# lora_gateway_sx1302_pcie_module_v1_1_868.net
KiCad netlist of a schematic drawn in EAGLE
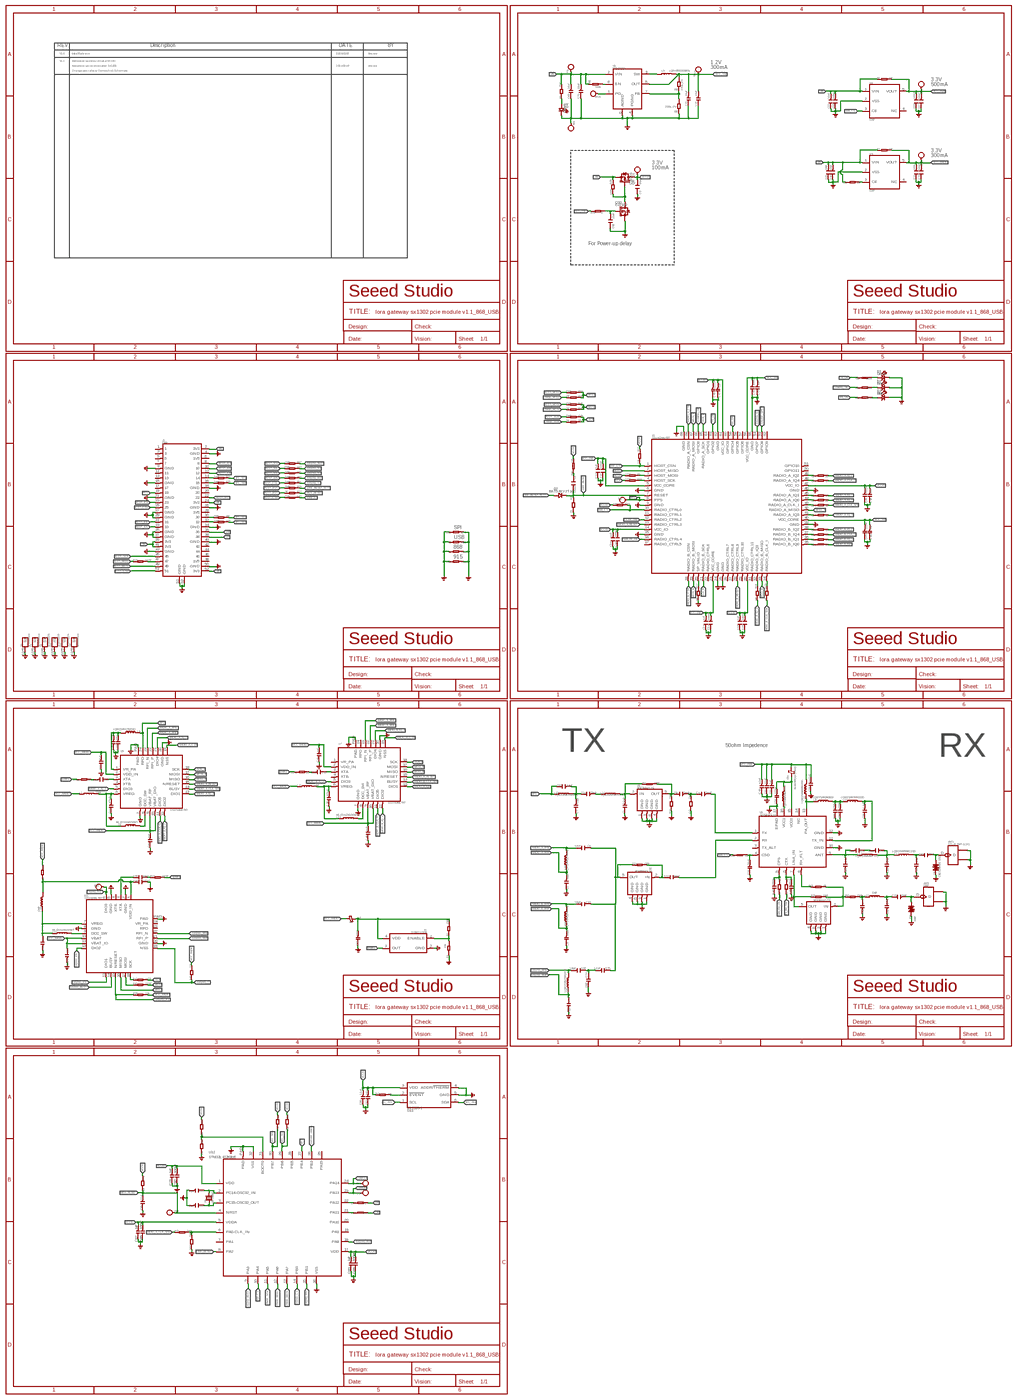
[diagram p0: schematic, sheet 1, overview]
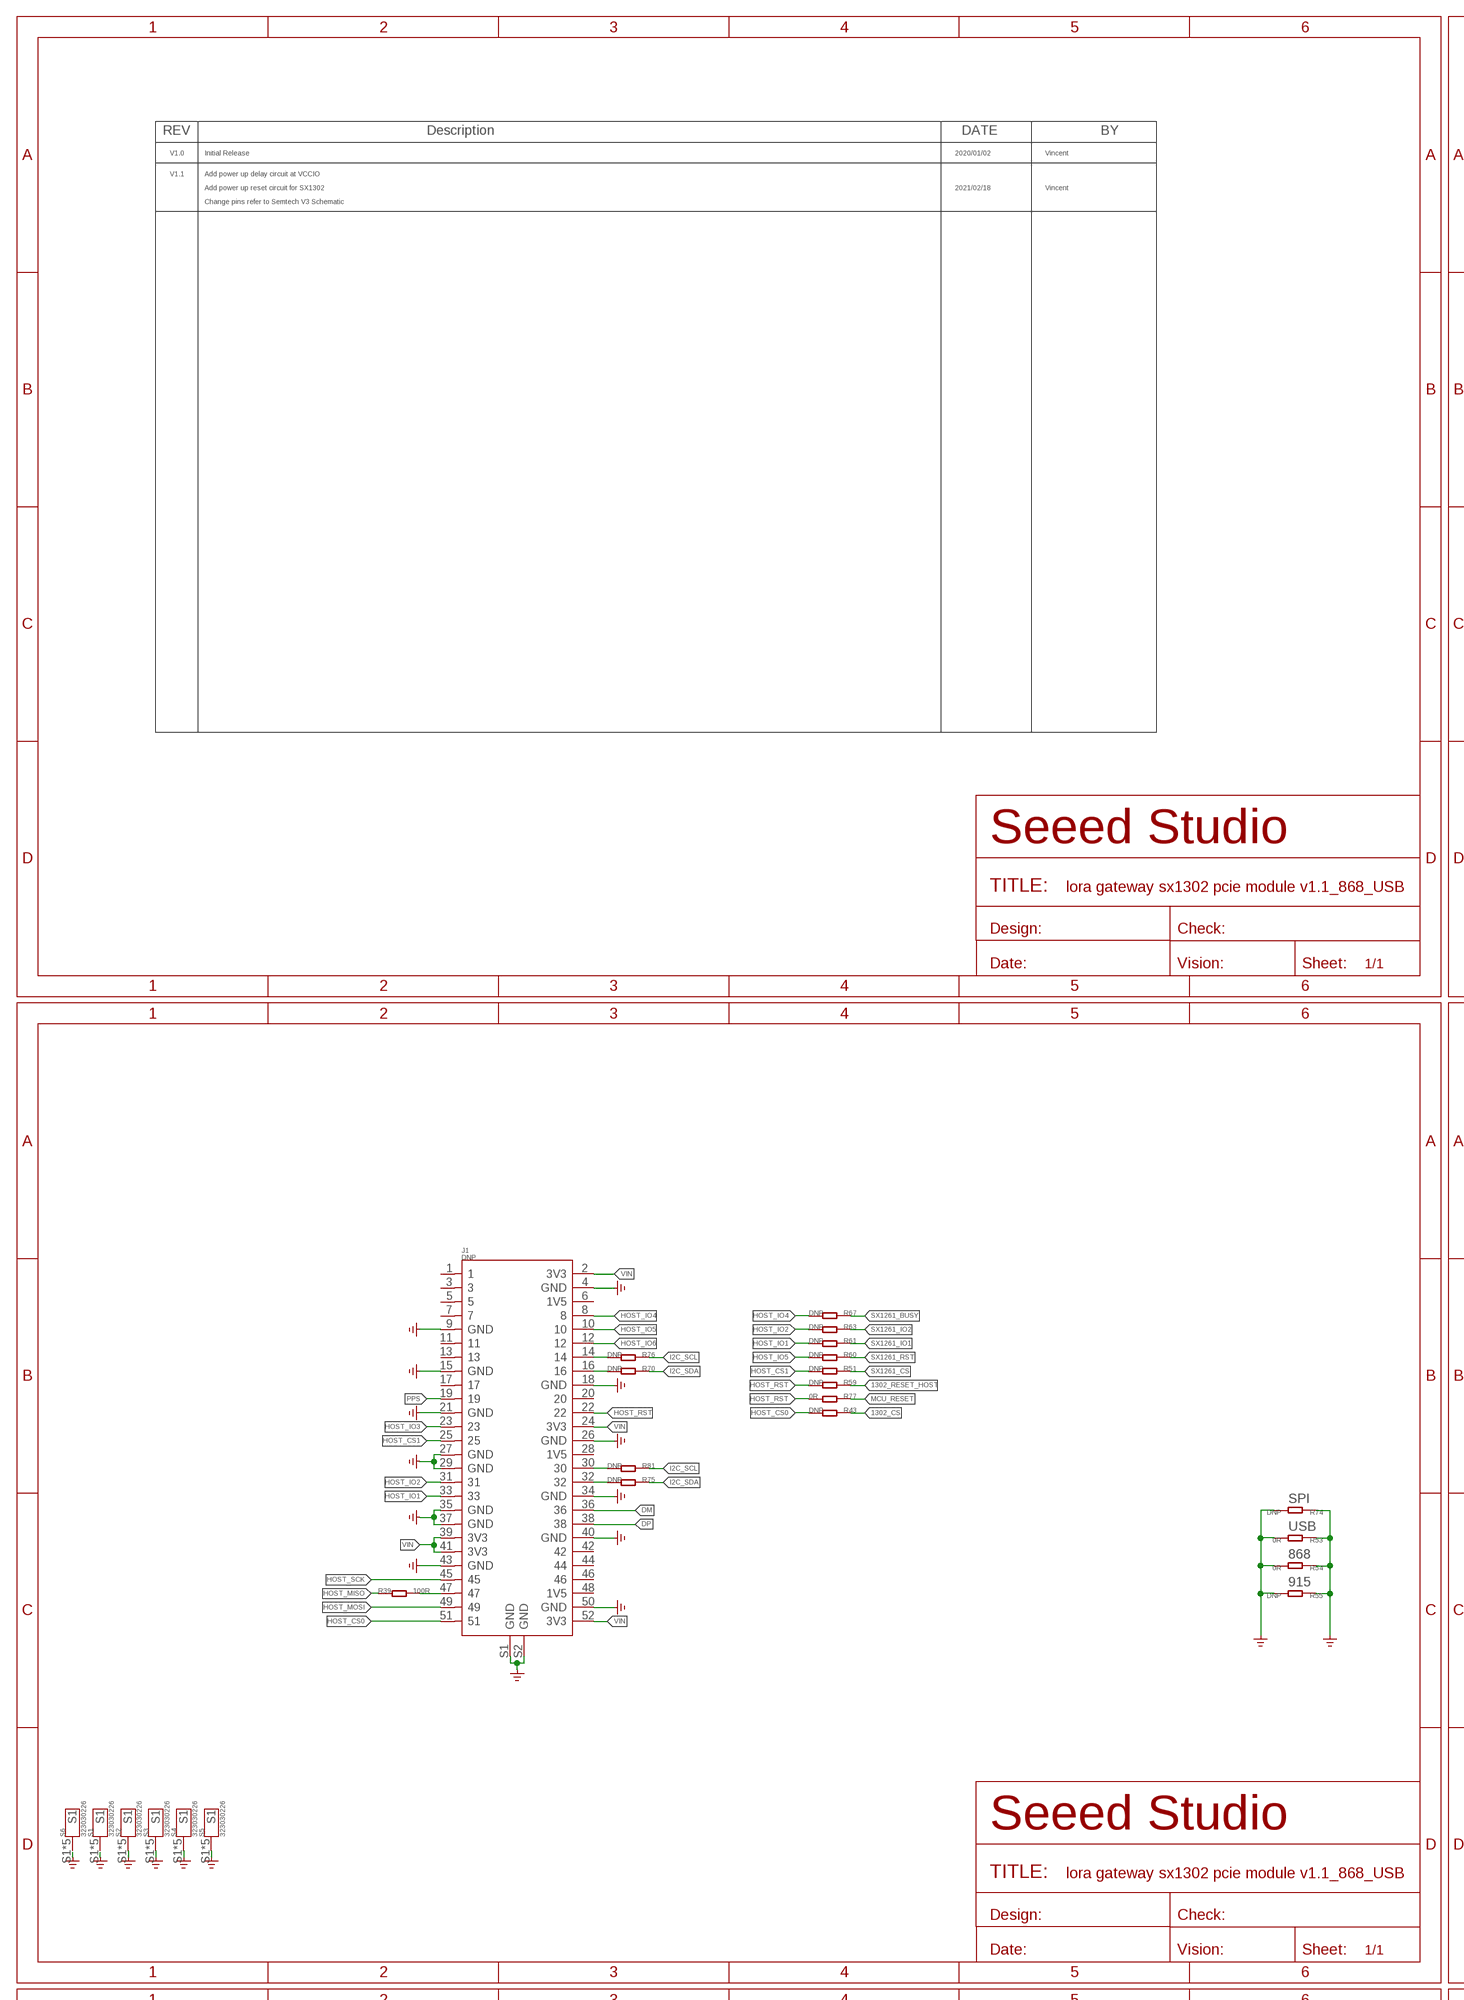
[diagram p1: schematic, sheet 1, part 1 of 4]
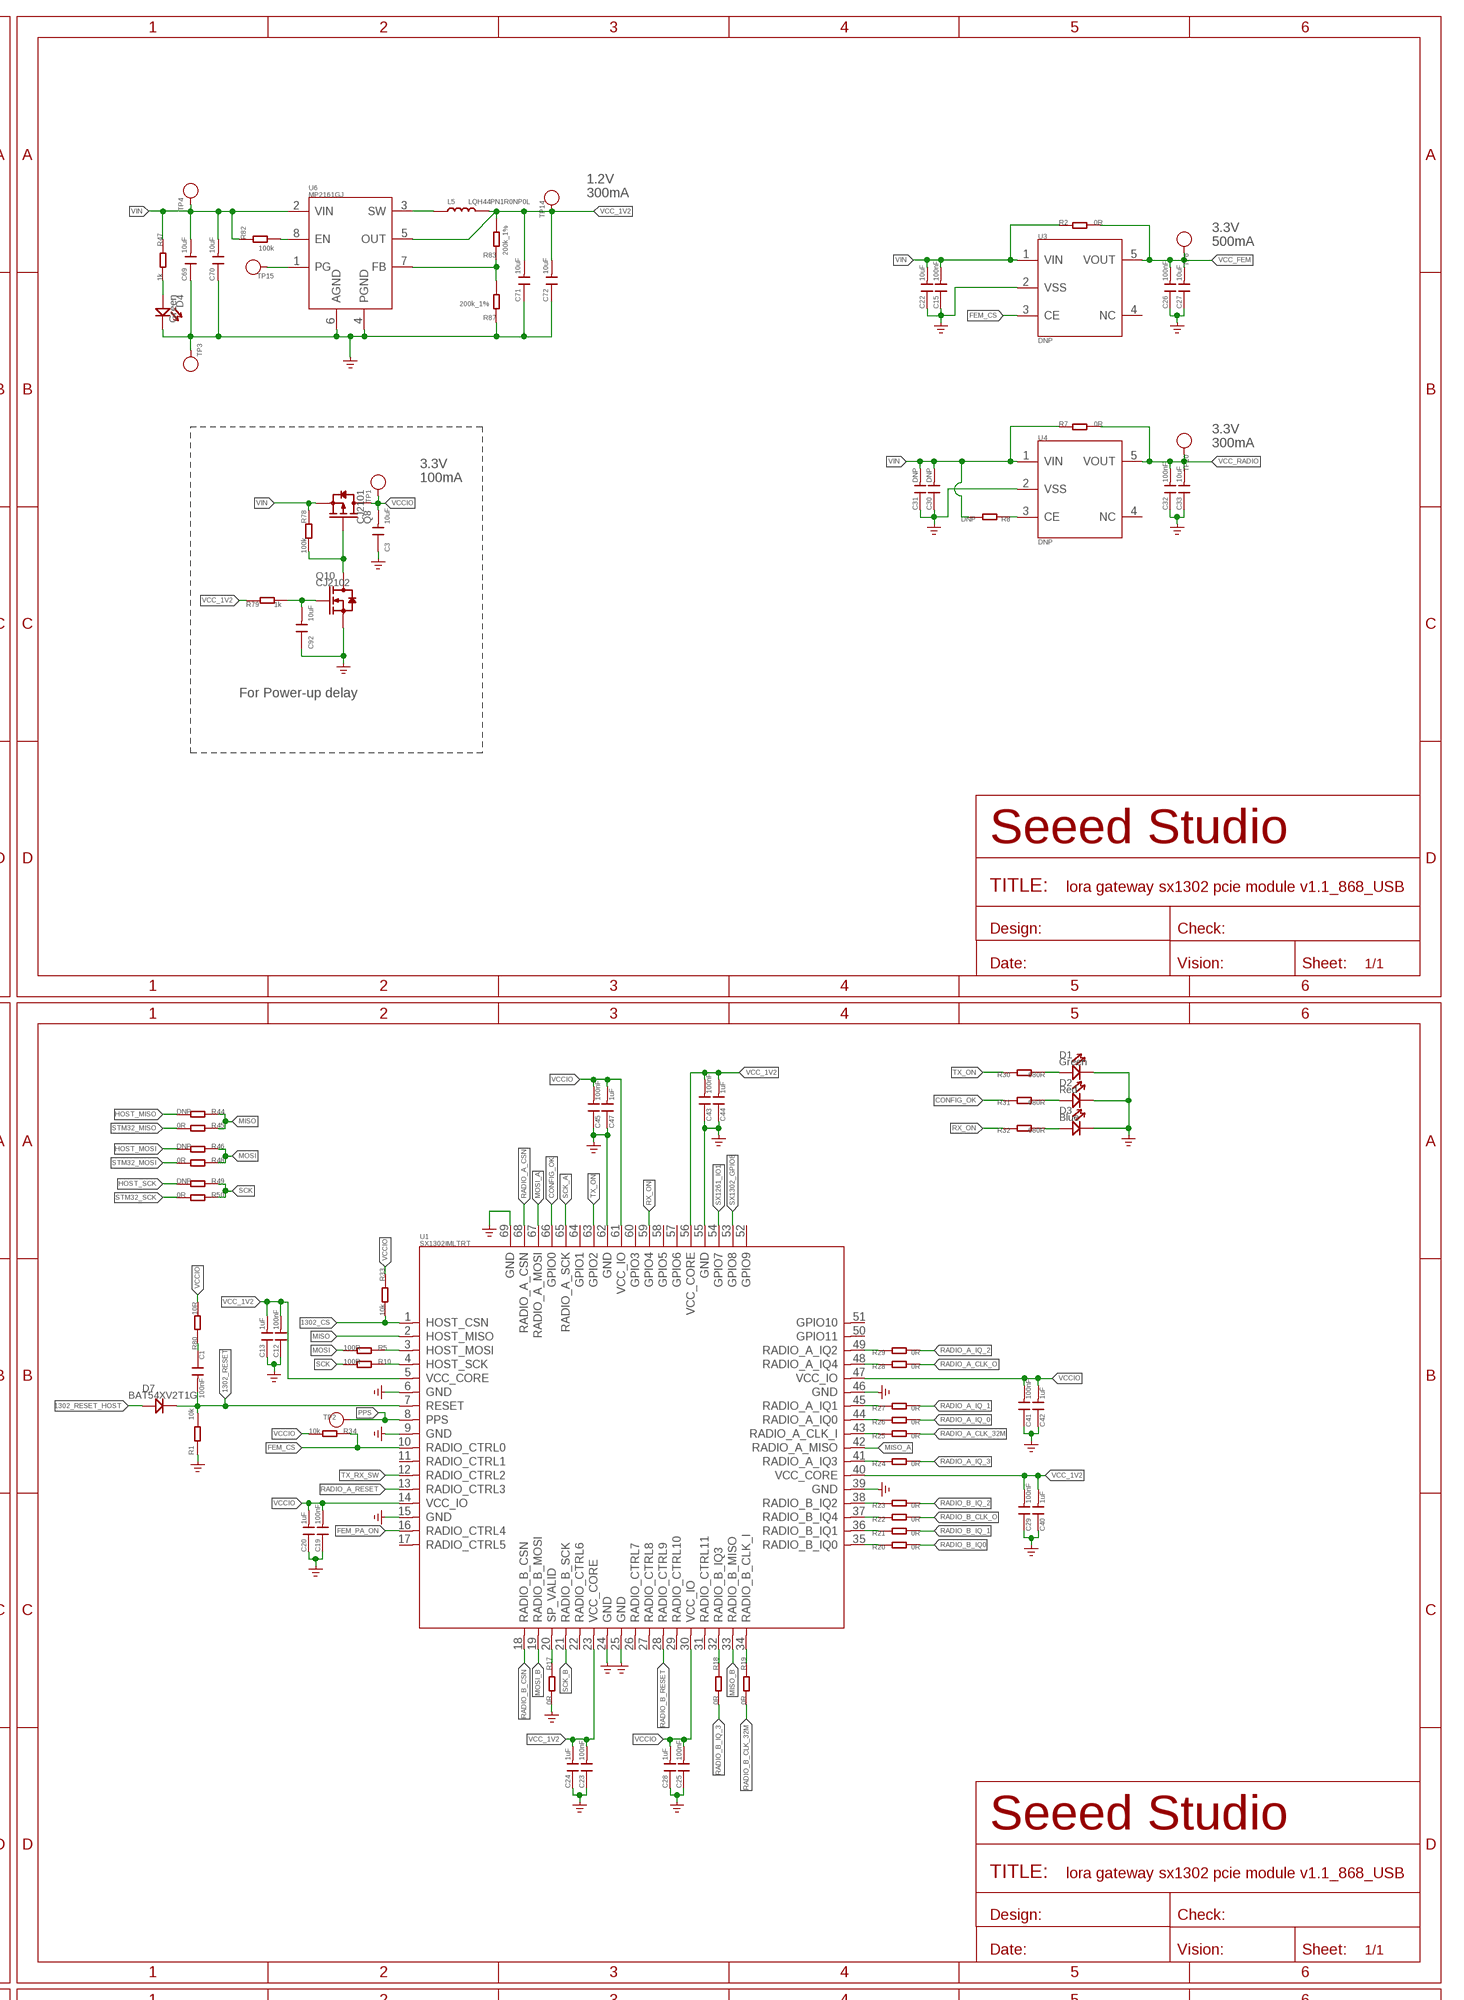
[diagram p2: schematic, sheet 1, part 2 of 4]
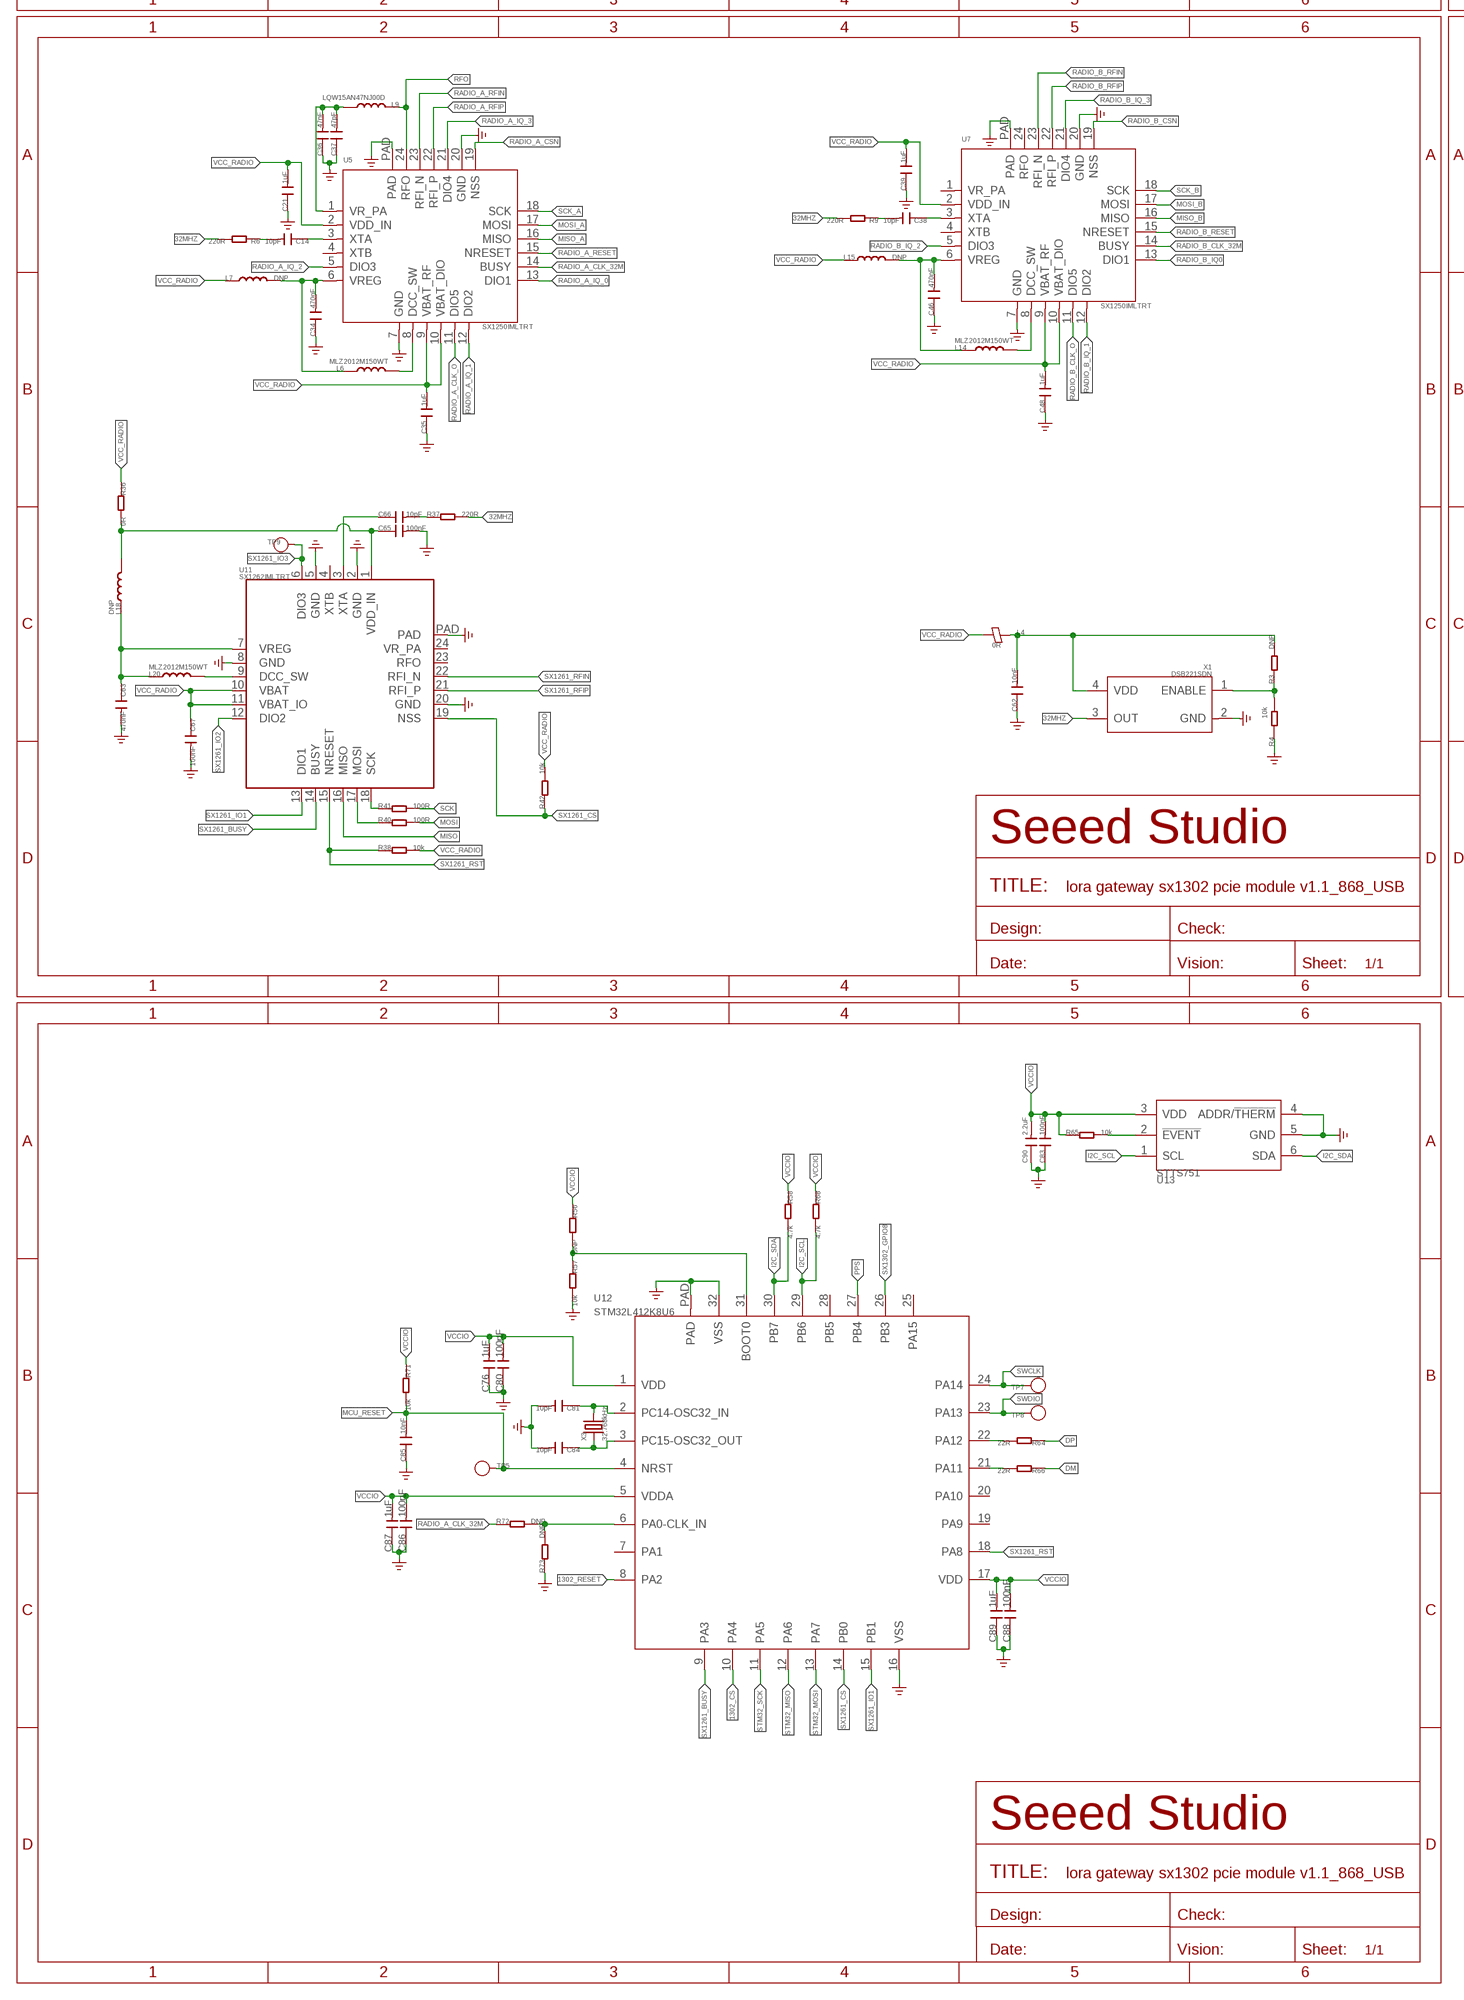
[diagram p3: schematic, sheet 1, part 3 of 4]
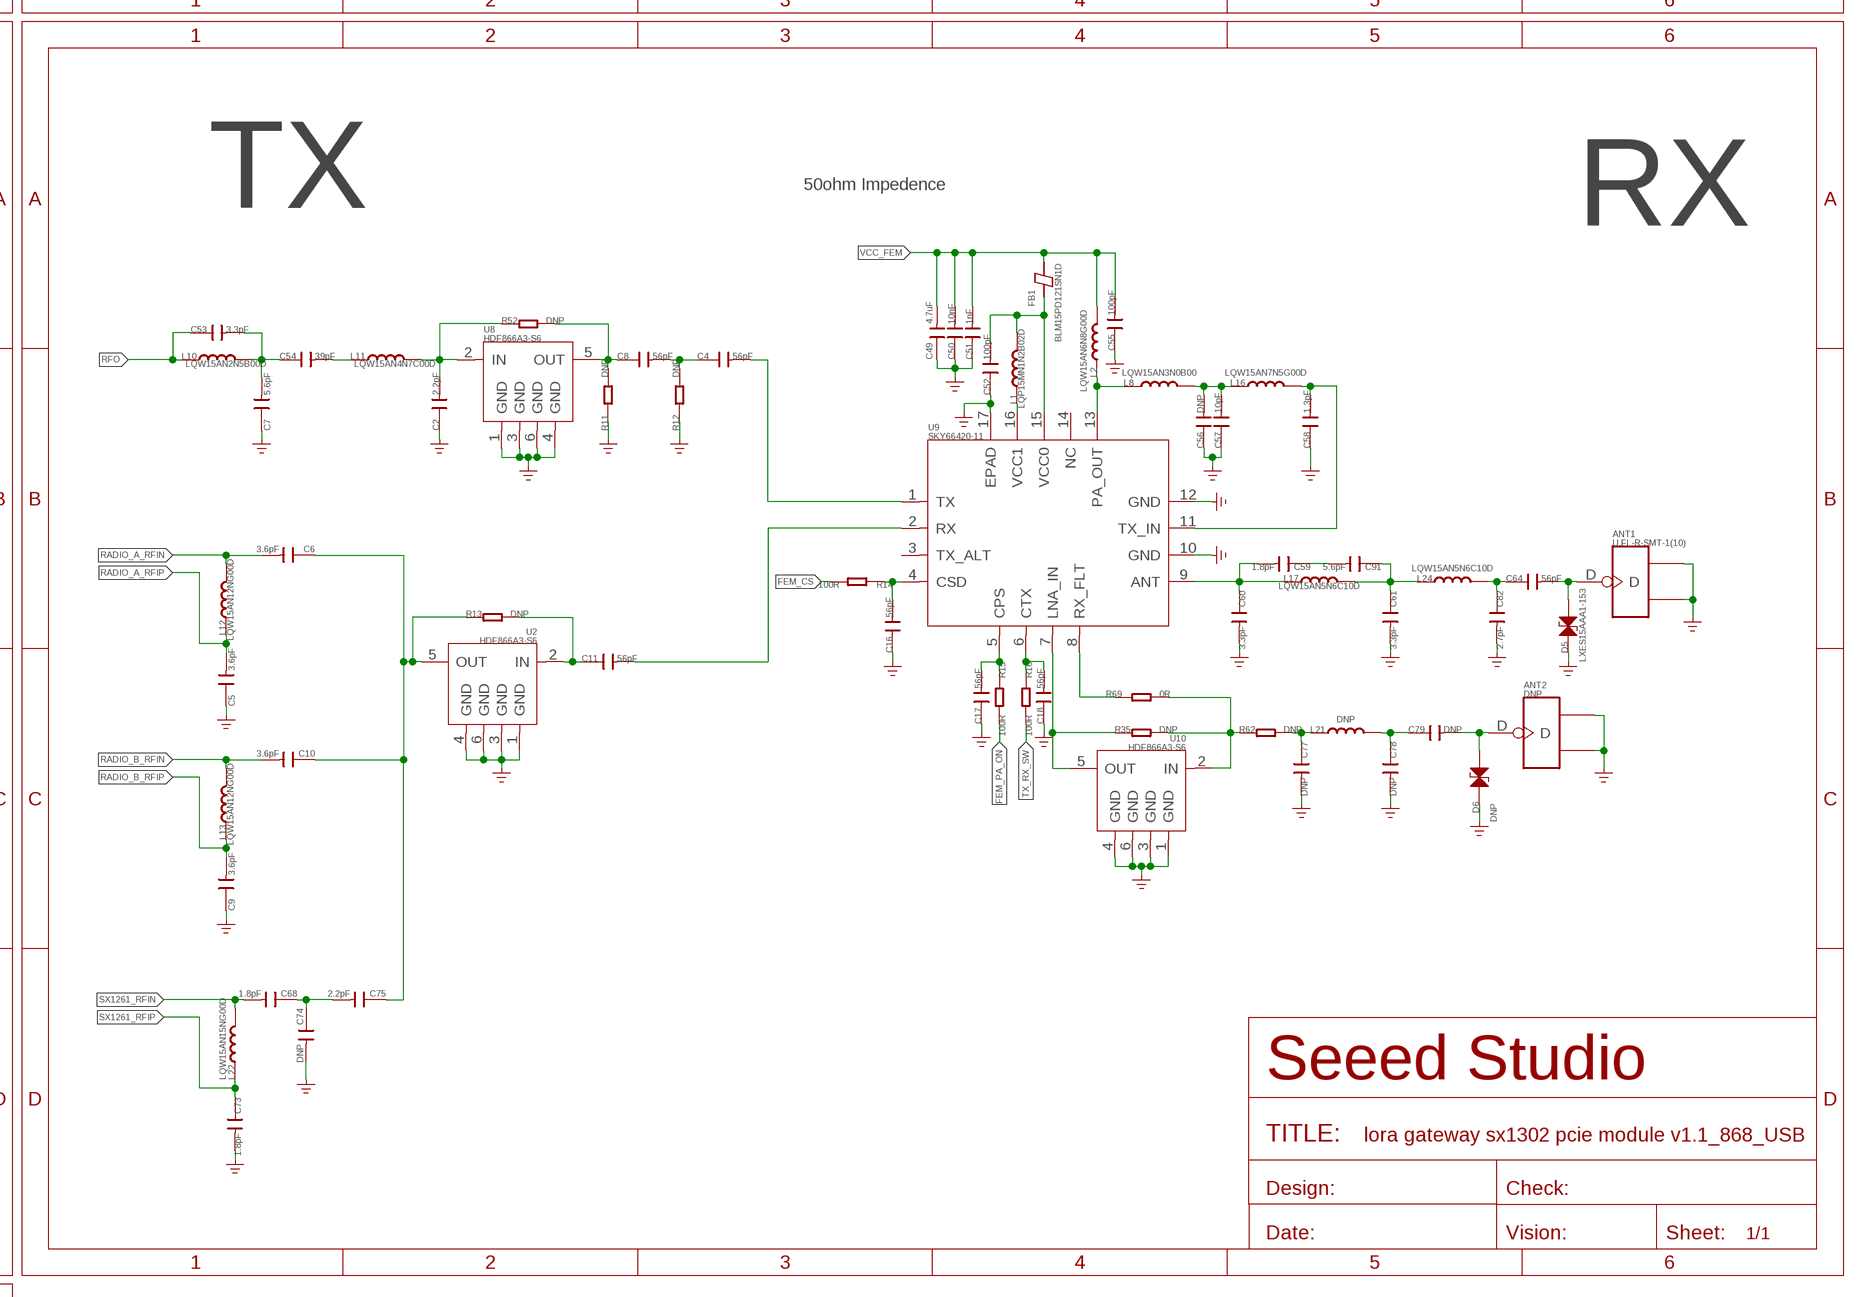
[diagram p4: schematic, sheet 1, part 4 of 4]

(export (version "E")
  (design (tool "Eeschema 10.0.6"))
  (components
    (comp (ref "ANT1")
      (value "U.FL-R-SMT-1(10)")
      (footprint "eagle-import:U-FL3P-SMD-2.6X2.6X1.0MM")
      (fields (field (name "SPICEPREFIX") "J"))
      (libsource (lib "eagle-import") (part "ANTENNA-U-FL-320110048"))
    )
    (comp (ref "ANT2")
      (value "DNP")
      (footprint "eagle-import:U-FL3P-SMD-2.6X2.6X1.0MM")
      (fields (field (name "SPICEPREFIX") "J"))
      (libsource (lib "eagle-import") (part "ANTENNA-U-FL-320110048"))
    )
    (comp (ref "C1")
      (value "100nF")
      (footprint "eagle-import:C0402")
      (libsource (lib "eagle-import") (part "C-0402"))
    )
    (comp (ref "C2")
      (value "2.2pF")
      (footprint "eagle-import:C0402")
      (libsource (lib "eagle-import") (part "C-0402"))
    )
    (comp (ref "C3")
      (value "10uF")
      (footprint "eagle-import:C0603")
      (libsource (lib "eagle-import") (part "C-0603"))
    )
    (comp (ref "C4")
      (value "56pF")
      (footprint "eagle-import:C0402")
      (libsource (lib "eagle-import") (part "C-0402"))
    )
    (comp (ref "C5")
      (value "3.6pF")
      (footprint "eagle-import:C0402")
      (libsource (lib "eagle-import") (part "C-0402"))
    )
    (comp (ref "C6")
      (value "3.6pF")
      (footprint "eagle-import:C0402")
      (libsource (lib "eagle-import") (part "C-0402"))
    )
    (comp (ref "C7")
      (value "5.6pF")
      (footprint "eagle-import:C0402")
      (libsource (lib "eagle-import") (part "C-0402"))
    )
    (comp (ref "C8")
      (value "56pF")
      (footprint "eagle-import:C0402")
      (libsource (lib "eagle-import") (part "C-0402"))
    )
    (comp (ref "C9")
      (value "3.6pF")
      (footprint "eagle-import:C0402")
      (libsource (lib "eagle-import") (part "C-0402"))
    )
    (comp (ref "C10")
      (value "3.6pF")
      (footprint "eagle-import:C0402")
      (libsource (lib "eagle-import") (part "C-0402"))
    )
    (comp (ref "C11")
      (value "56pF")
      (footprint "eagle-import:C0402")
      (libsource (lib "eagle-import") (part "C-0402"))
    )
    (comp (ref "C12")
      (value "100nF")
      (footprint "eagle-import:C0402")
      (libsource (lib "eagle-import") (part "C-0402"))
    )
    (comp (ref "C13")
      (value "1uF")
      (footprint "eagle-import:C0402")
      (libsource (lib "eagle-import") (part "C-0402"))
    )
    (comp (ref "C14")
      (value "10pF")
      (footprint "eagle-import:C0402")
      (libsource (lib "eagle-import") (part "C-0402"))
    )
    (comp (ref "C15")
      (value "100nF")
      (footprint "eagle-import:C0402")
      (libsource (lib "eagle-import") (part "C-0402"))
    )
    (comp (ref "C16")
      (value "56pF")
      (footprint "eagle-import:C0402")
      (libsource (lib "eagle-import") (part "C-0402"))
    )
    (comp (ref "C17")
      (value "56pF")
      (footprint "eagle-import:C0402")
      (libsource (lib "eagle-import") (part "C-0402"))
    )
    (comp (ref "C18")
      (value "56pF")
      (footprint "eagle-import:C0402")
      (libsource (lib "eagle-import") (part "C-0402"))
    )
    (comp (ref "C19")
      (value "100nF")
      (footprint "eagle-import:C0402")
      (libsource (lib "eagle-import") (part "C-0402"))
    )
    (comp (ref "C20")
      (value "1uF")
      (footprint "eagle-import:C0402")
      (libsource (lib "eagle-import") (part "C-0402"))
    )
    (comp (ref "C21")
      (value "1uF")
      (footprint "eagle-import:C0402")
      (libsource (lib "eagle-import") (part "C-0402"))
    )
    (comp (ref "C22")
      (value "10uF")
      (footprint "eagle-import:C0603@1")
      (libsource (lib "eagle-import") (part "CAP-0603"))
    )
    (comp (ref "C23")
      (value "100nF")
      (footprint "eagle-import:C0402")
      (libsource (lib "eagle-import") (part "C-0402"))
    )
    (comp (ref "C24")
      (value "1uF")
      (footprint "eagle-import:C0402")
      (libsource (lib "eagle-import") (part "C-0402"))
    )
    (comp (ref "C25")
      (value "100nF")
      (footprint "eagle-import:C0402")
      (libsource (lib "eagle-import") (part "C-0402"))
    )
    (comp (ref "C26")
      (value "100nF")
      (footprint "eagle-import:C0402")
      (libsource (lib "eagle-import") (part "C-0402"))
    )
    (comp (ref "C27")
      (value "10uF")
      (footprint "eagle-import:C0603@1")
      (libsource (lib "eagle-import") (part "CAP-0603"))
    )
    (comp (ref "C28")
      (value "1uF")
      (footprint "eagle-import:C0402")
      (libsource (lib "eagle-import") (part "C-0402"))
    )
    (comp (ref "C29")
      (value "100nF")
      (footprint "eagle-import:C0402")
      (libsource (lib "eagle-import") (part "C-0402"))
    )
    (comp (ref "C30")
      (value "DNP")
      (footprint "eagle-import:C0402")
      (libsource (lib "eagle-import") (part "C-0402"))
    )
    (comp (ref "C31")
      (value "DNP")
      (footprint "eagle-import:C0603@1")
      (libsource (lib "eagle-import") (part "CAP-0603"))
    )
    (comp (ref "C32")
      (value "100nF")
      (footprint "eagle-import:C0402")
      (libsource (lib "eagle-import") (part "C-0402"))
    )
    (comp (ref "C33")
      (value "10uF")
      (footprint "eagle-import:C0603@1")
      (libsource (lib "eagle-import") (part "CAP-0603"))
    )
    (comp (ref "C34")
      (value "470nF")
      (footprint "eagle-import:C0402")
      (libsource (lib "eagle-import") (part "C-0402"))
    )
    (comp (ref "C35")
      (value "1uF")
      (footprint "eagle-import:C0402")
      (libsource (lib "eagle-import") (part "C-0402"))
    )
    (comp (ref "C36")
      (value "47nF")
      (footprint "eagle-import:C0402")
      (libsource (lib "eagle-import") (part "C-0402"))
    )
    (comp (ref "C37")
      (value "47pF")
      (footprint "eagle-import:C0402")
      (libsource (lib "eagle-import") (part "C-0402"))
    )
    (comp (ref "C38")
      (value "10pF")
      (footprint "eagle-import:C0402")
      (libsource (lib "eagle-import") (part "C-0402"))
    )
    (comp (ref "C39")
      (value "1uF")
      (footprint "eagle-import:C0402")
      (libsource (lib "eagle-import") (part "C-0402"))
    )
    (comp (ref "C40")
      (value "1uF")
      (footprint "eagle-import:C0402")
      (libsource (lib "eagle-import") (part "C-0402"))
    )
    (comp (ref "C41")
      (value "100nF")
      (footprint "eagle-import:C0402")
      (libsource (lib "eagle-import") (part "C-0402"))
    )
    (comp (ref "C42")
      (value "1uF")
      (footprint "eagle-import:C0402")
      (libsource (lib "eagle-import") (part "C-0402"))
    )
    (comp (ref "C43")
      (value "100nF")
      (footprint "eagle-import:C0402")
      (libsource (lib "eagle-import") (part "C-0402"))
    )
    (comp (ref "C44")
      (value "1uF")
      (footprint "eagle-import:C0402")
      (libsource (lib "eagle-import") (part "C-0402"))
    )
    (comp (ref "C45")
      (value "100nF")
      (footprint "eagle-import:C0402")
      (libsource (lib "eagle-import") (part "C-0402"))
    )
    (comp (ref "C46")
      (value "470nF")
      (footprint "eagle-import:C0402")
      (libsource (lib "eagle-import") (part "C-0402"))
    )
    (comp (ref "C47")
      (value "1uF")
      (footprint "eagle-import:C0402")
      (libsource (lib "eagle-import") (part "C-0402"))
    )
    (comp (ref "C48")
      (value "1uF")
      (footprint "eagle-import:C0402")
      (libsource (lib "eagle-import") (part "C-0402"))
    )
    (comp (ref "C49")
      (value "4.7uF")
      (footprint "eagle-import:C0603")
      (libsource (lib "eagle-import") (part "C-0603"))
    )
    (comp (ref "C50")
      (value "10nF")
      (footprint "eagle-import:C0402")
      (libsource (lib "eagle-import") (part "C-0402"))
    )
    (comp (ref "C51")
      (value "1nF")
      (footprint "eagle-import:C0402")
      (libsource (lib "eagle-import") (part "C-0402"))
    )
    (comp (ref "C52")
      (value "100pF")
      (footprint "eagle-import:C0402")
      (libsource (lib "eagle-import") (part "C-0402"))
    )
    (comp (ref "C53")
      (value "3.3pF")
      (footprint "eagle-import:C0402")
      (libsource (lib "eagle-import") (part "C-0402"))
    )
    (comp (ref "C54")
      (value "39pF")
      (footprint "eagle-import:C0402")
      (libsource (lib "eagle-import") (part "C-0402"))
    )
    (comp (ref "C55")
      (value "100pF")
      (footprint "eagle-import:C0402")
      (fields (field (name "SPICEPREFIX") "C"))
      (libsource (lib "eagle-import") (part "C-0402"))
    )
    (comp (ref "C56")
      (value "DNP")
      (footprint "eagle-import:C0402")
      (libsource (lib "eagle-import") (part "C-0402"))
    )
    (comp (ref "C57")
      (value "10pF")
      (footprint "eagle-import:C0402")
      (libsource (lib "eagle-import") (part "C-0402"))
    )
    (comp (ref "C58")
      (value "1.3pF")
      (footprint "eagle-import:C0402")
      (libsource (lib "eagle-import") (part "C-0402"))
    )
    (comp (ref "C59")
      (value "1.8pF")
      (footprint "eagle-import:C0402")
      (libsource (lib "eagle-import") (part "C-0402"))
    )
    (comp (ref "C60")
      (value "3.3pF")
      (footprint "eagle-import:C0402")
      (libsource (lib "eagle-import") (part "C-0402"))
    )
    (comp (ref "C61")
      (value "3.3pF")
      (footprint "eagle-import:C0402")
      (libsource (lib "eagle-import") (part "C-0402"))
    )
    (comp (ref "C62")
      (value "10nF")
      (footprint "eagle-import:C0402")
      (libsource (lib "eagle-import") (part "C-0402"))
    )
    (comp (ref "C63")
      (value "470nF")
      (footprint "eagle-import:C0402")
      (libsource (lib "eagle-import") (part "C-0402"))
    )
    (comp (ref "C64")
      (value "56pF")
      (footprint "eagle-import:C0402")
      (libsource (lib "eagle-import") (part "C-0402"))
    )
    (comp (ref "C65")
      (value "100nF")
      (footprint "eagle-import:C0402")
      (libsource (lib "eagle-import") (part "C-0402"))
    )
    (comp (ref "C66")
      (value "10pF")
      (footprint "eagle-import:C0402")
      (libsource (lib "eagle-import") (part "C-0402"))
    )
    (comp (ref "C67")
      (value "100nF")
      (footprint "eagle-import:C0402")
      (libsource (lib "eagle-import") (part "C-0402"))
    )
    (comp (ref "C68")
      (value "1.8pF")
      (footprint "eagle-import:C0402")
      (libsource (lib "eagle-import") (part "C-0402"))
    )
    (comp (ref "C69")
      (value "10uF")
      (footprint "eagle-import:C0805")
      (libsource (lib "eagle-import") (part "CAP-0805"))
    )
    (comp (ref "C70")
      (value "10uF")
      (footprint "eagle-import:C0805")
      (libsource (lib "eagle-import") (part "CAP-0805"))
    )
    (comp (ref "C71")
      (value "10uF")
      (footprint "eagle-import:C0805")
      (libsource (lib "eagle-import") (part "CAP-0805"))
    )
    (comp (ref "C72")
      (value "10uF")
      (footprint "eagle-import:C0805")
      (libsource (lib "eagle-import") (part "CAP-0805"))
    )
    (comp (ref "C73")
      (value "1.8pF")
      (footprint "eagle-import:C0402")
      (libsource (lib "eagle-import") (part "C-0402"))
    )
    (comp (ref "C74")
      (value "DNP")
      (footprint "eagle-import:C0402")
      (libsource (lib "eagle-import") (part "C-0402"))
    )
    (comp (ref "C75")
      (value "2.2pF")
      (footprint "eagle-import:C0402")
      (libsource (lib "eagle-import") (part "C-0402"))
    )
    (comp (ref "C76")
      (value "1uF")
      (footprint "eagle-import:C0402")
      (libsource (lib "eagle-import") (part "C-0402"))
    )
    (comp (ref "C77")
      (value "DNP")
      (footprint "eagle-import:C0402")
      (libsource (lib "eagle-import") (part "C-0402"))
    )
    (comp (ref "C78")
      (value "DNP")
      (footprint "eagle-import:C0402")
      (libsource (lib "eagle-import") (part "C-0402"))
    )
    (comp (ref "C79")
      (value "DNP")
      (footprint "eagle-import:C0402")
      (libsource (lib "eagle-import") (part "C-0402"))
    )
    (comp (ref "C80")
      (value "100nF")
      (footprint "eagle-import:C0402")
      (libsource (lib "eagle-import") (part "C-0402"))
    )
    (comp (ref "C81")
      (value "10pF")
      (footprint "eagle-import:C0402")
      (libsource (lib "eagle-import") (part "C-0402"))
    )
    (comp (ref "C82")
      (value "2.7pF")
      (footprint "eagle-import:C0402")
      (libsource (lib "eagle-import") (part "C-0402"))
    )
    (comp (ref "C83")
      (value "100nF")
      (footprint "eagle-import:C0402")
      (libsource (lib "eagle-import") (part "C-0402"))
    )
    (comp (ref "C84")
      (value "10pF")
      (footprint "eagle-import:C0402")
      (libsource (lib "eagle-import") (part "C-0402"))
    )
    (comp (ref "C85")
      (value "10nF")
      (footprint "eagle-import:C0402")
      (libsource (lib "eagle-import") (part "C-0402"))
    )
    (comp (ref "C86")
      (value "100nF")
      (footprint "eagle-import:C0402")
      (libsource (lib "eagle-import") (part "C-0402"))
    )
    (comp (ref "C87")
      (value "1uF")
      (footprint "eagle-import:C0402")
      (libsource (lib "eagle-import") (part "C-0402"))
    )
    (comp (ref "C88")
      (value "100nF")
      (footprint "eagle-import:C0402")
      (libsource (lib "eagle-import") (part "C-0402"))
    )
    (comp (ref "C89")
      (value "1uF")
      (footprint "eagle-import:C0402")
      (libsource (lib "eagle-import") (part "C-0402"))
    )
    (comp (ref "C90")
      (value "2.2uF")
      (footprint "eagle-import:C0603")
      (libsource (lib "eagle-import") (part "C-0603"))
    )
    (comp (ref "C91")
      (value "5.6pF")
      (footprint "eagle-import:C0402")
      (libsource (lib "eagle-import") (part "C-0402"))
    )
    (comp (ref "C92")
      (value "10uF")
      (footprint "eagle-import:C0603")
      (libsource (lib "eagle-import") (part "C-0603"))
    )
    (comp (ref "D1")
      (value "Green")
      (footprint "eagle-import:LED-0402")
      (libsource (lib "eagle-import") (part "LED-0402"))
    )
    (comp (ref "D2")
      (value "Red")
      (footprint "eagle-import:LED-0402")
      (libsource (lib "eagle-import") (part "LED-0402"))
    )
    (comp (ref "D3")
      (value "Blue")
      (footprint "eagle-import:LED-0402")
      (libsource (lib "eagle-import") (part "LED-0402"))
    )
    (comp (ref "D4")
      (value "Green")
      (footprint "eagle-import:LED-0402")
      (libsource (lib "eagle-import") (part "LED-0402"))
    )
    (comp (ref "D5")
      (value "LXES15AAA1-153")
      (footprint "eagle-import:ESD-0402")
      (libsource (lib "eagle-import") (part "D-ESD-2P-DOUBLE-0402"))
    )
    (comp (ref "D6")
      (value "DNP")
      (footprint "eagle-import:ESD-0402")
      (libsource (lib "eagle-import") (part "D-ESD-2P-DOUBLE-0402"))
    )
    (comp (ref "D7")
      (value "BAT54XV2T1G")
      (footprint "eagle-import:SOD-523")
      (libsource (lib "eagle-import") (part "DIODE'0603'"))
    )
    (comp (ref "FB1")
      (value "BLM15PD121SN1D")
      (footprint "eagle-import:F0402")
      (libsource (lib "eagle-import") (part "FERRITE-BEAD-0402"))
    )
    (comp (ref "J1")
      (value "DNP")
      (footprint "eagle-import:PCIE52P-0.8-50.95X30MM")
      (libsource (lib "eagle-import") (part "MOUDLE-FULL-MINI-PCIE"))
    )
    (comp (ref "L1")
      (value "LQP15MN1N2B02D")
      (footprint "eagle-import:L0402")
      (libsource (lib "eagle-import") (part "L-0402"))
    )
    (comp (ref "L2")
      (value "LQW15AN6N8G00D")
      (footprint "eagle-import:L0402")
      (libsource (lib "eagle-import") (part "L-0402"))
    )
    (comp (ref "L4")
      (value "0R")
      (footprint "eagle-import:F0603")
      (libsource (lib "eagle-import") (part "FERRITE-BEAD-0603"))
    )
    (comp (ref "L5")
      (value "LQH44PN1R0NP0L")
      (footprint "eagle-import:L4.4X3.0MM")
      (libsource (lib "eagle-import") (part "INDUCTOR-4430"))
    )
    (comp (ref "L6")
      (value "MLZ2012M150WT")
      (footprint "eagle-import:L0805")
      (libsource (lib "eagle-import") (part "L-0805"))
    )
    (comp (ref "L7")
      (value "DNP")
      (footprint "eagle-import:L0402")
      (libsource (lib "eagle-import") (part "L-0402"))
    )
    (comp (ref "L8")
      (value "LQW15AN3N0B00")
      (footprint "eagle-import:L0402")
      (libsource (lib "eagle-import") (part "L-0402"))
    )
    (comp (ref "L9")
      (value "LQW15AN47NJ00D")
      (footprint "eagle-import:L0402")
      (libsource (lib "eagle-import") (part "L-0402"))
    )
    (comp (ref "L10")
      (value "LQW15AN2N5B00D")
      (footprint "eagle-import:L0402")
      (libsource (lib "eagle-import") (part "L-0402"))
    )
    (comp (ref "L11")
      (value "LQW15AN4N7C00D")
      (footprint "eagle-import:L0402")
      (libsource (lib "eagle-import") (part "L-0402"))
    )
    (comp (ref "L12")
      (value "LQW15AN12NG00D")
      (footprint "eagle-import:L0402")
      (libsource (lib "eagle-import") (part "L-0402"))
    )
    (comp (ref "L13")
      (value "LQW15AN12NG00D")
      (footprint "eagle-import:L0402")
      (libsource (lib "eagle-import") (part "L-0402"))
    )
    (comp (ref "L14")
      (value "MLZ2012M150WT")
      (footprint "eagle-import:L0805")
      (libsource (lib "eagle-import") (part "L-0805"))
    )
    (comp (ref "L15")
      (value "DNP")
      (footprint "eagle-import:L0402")
      (libsource (lib "eagle-import") (part "L-0402"))
    )
    (comp (ref "L16")
      (value "LQW15AN7N5G00D")
      (footprint "eagle-import:L0402")
      (libsource (lib "eagle-import") (part "L-0402"))
    )
    (comp (ref "L17")
      (value "LQW15AN5N6C10D")
      (footprint "eagle-import:L0402")
      (libsource (lib "eagle-import") (part "L-0402"))
    )
    (comp (ref "L18")
      (value "DNP")
      (footprint "eagle-import:L0402")
      (libsource (lib "eagle-import") (part "L-0402"))
    )
    (comp (ref "L20")
      (value "MLZ2012M150WT")
      (footprint "eagle-import:L0805")
      (libsource (lib "eagle-import") (part "L-0805"))
    )
    (comp (ref "L21")
      (value "DNP")
      (footprint "eagle-import:L0402")
      (libsource (lib "eagle-import") (part "L-0402"))
    )
    (comp (ref "L22")
      (value "LQW15AN15NG00D")
      (footprint "eagle-import:L0402")
      (libsource (lib "eagle-import") (part "L-0402"))
    )
    (comp (ref "L24")
      (value "LQW15AN5N6C10D")
      (footprint "eagle-import:L0402")
      (libsource (lib "eagle-import") (part "L-0402"))
    )
    (comp (ref "Q8")
      (value "CJ2101")
      (footprint "eagle-import:SOT-323")
      (libsource (lib "eagle-import") (part "MOSFET-P-SOT323"))
    )
    (comp (ref "Q10")
      (value "CJ2102")
      (footprint "eagle-import:SOT-323")
      (libsource (lib "eagle-import") (part "MOSFET-N-SI1304BDL"))
    )
    (comp (ref "R1")
      (value "10k")
      (footprint "eagle-import:R0402")
      (libsource (lib "eagle-import") (part "R-0402"))
    )
    (comp (ref "R2")
      (value "0R")
      (footprint "eagle-import:R0603")
      (libsource (lib "eagle-import") (part "R-0603"))
    )
    (comp (ref "R3")
      (value "DNP")
      (footprint "eagle-import:R0402")
      (libsource (lib "eagle-import") (part "R-0402"))
    )
    (comp (ref "R4")
      (value "10k")
      (footprint "eagle-import:R0402")
      (libsource (lib "eagle-import") (part "R-0402"))
    )
    (comp (ref "R5")
      (value "100R")
      (footprint "eagle-import:R0402")
      (libsource (lib "eagle-import") (part "R-0402"))
    )
    (comp (ref "R6")
      (value "220R")
      (footprint "eagle-import:R0402")
      (libsource (lib "eagle-import") (part "R-0402"))
    )
    (comp (ref "R7")
      (value "0R")
      (footprint "eagle-import:R0603")
      (libsource (lib "eagle-import") (part "R-0603"))
    )
    (comp (ref "R8")
      (value "DNP")
      (footprint "eagle-import:R0402")
      (libsource (lib "eagle-import") (part "R-0402"))
    )
    (comp (ref "R9")
      (value "220R")
      (footprint "eagle-import:R0402")
      (libsource (lib "eagle-import") (part "R-0402"))
    )
    (comp (ref "R10")
      (value "100R")
      (footprint "eagle-import:R0402")
      (libsource (lib "eagle-import") (part "R-0402"))
    )
    (comp (ref "R11")
      (value "DNP")
      (footprint "eagle-import:R0402")
      (libsource (lib "eagle-import") (part "R-0402"))
    )
    (comp (ref "R12")
      (value "DNP")
      (footprint "eagle-import:R0402")
      (libsource (lib "eagle-import") (part "R-0402"))
    )
    (comp (ref "R13")
      (value "DNP")
      (footprint "eagle-import:R0603")
      (libsource (lib "eagle-import") (part "RES-0603"))
    )
    (comp (ref "R14")
      (value "100R")
      (footprint "eagle-import:R0402")
      (libsource (lib "eagle-import") (part "R-0402"))
    )
    (comp (ref "R15")
      (value "100R")
      (footprint "eagle-import:R0402")
      (libsource (lib "eagle-import") (part "R-0402"))
    )
    (comp (ref "R16")
      (value "100R")
      (footprint "eagle-import:R0402")
      (libsource (lib "eagle-import") (part "R-0402"))
    )
    (comp (ref "R17")
      (value "0R")
      (footprint "eagle-import:R0402")
      (libsource (lib "eagle-import") (part "R-0402"))
    )
    (comp (ref "R18")
      (value "0R")
      (footprint "eagle-import:R0402")
      (libsource (lib "eagle-import") (part "R-0402"))
    )
    (comp (ref "R19")
      (value "0R")
      (footprint "eagle-import:R0402")
      (libsource (lib "eagle-import") (part "R-0402"))
    )
    (comp (ref "R20")
      (value "0R")
      (footprint "eagle-import:R0402")
      (libsource (lib "eagle-import") (part "R-0402"))
    )
    (comp (ref "R21")
      (value "0R")
      (footprint "eagle-import:R0402")
      (libsource (lib "eagle-import") (part "R-0402"))
    )
    (comp (ref "R22")
      (value "0R")
      (footprint "eagle-import:R0402")
      (libsource (lib "eagle-import") (part "R-0402"))
    )
    (comp (ref "R23")
      (value "0R")
      (footprint "eagle-import:R0402")
      (libsource (lib "eagle-import") (part "R-0402"))
    )
    (comp (ref "R24")
      (value "0R")
      (footprint "eagle-import:R0402")
      (libsource (lib "eagle-import") (part "R-0402"))
    )
    (comp (ref "R25")
      (value "0R")
      (footprint "eagle-import:R0402")
      (libsource (lib "eagle-import") (part "R-0402"))
    )
    (comp (ref "R26")
      (value "0R")
      (footprint "eagle-import:R0402")
      (libsource (lib "eagle-import") (part "R-0402"))
    )
    (comp (ref "R27")
      (value "0R")
      (footprint "eagle-import:R0402")
      (libsource (lib "eagle-import") (part "R-0402"))
    )
    (comp (ref "R28")
      (value "0R")
      (footprint "eagle-import:R0402")
      (libsource (lib "eagle-import") (part "R-0402"))
    )
    (comp (ref "R29")
      (value "0R")
      (footprint "eagle-import:R0402")
      (libsource (lib "eagle-import") (part "R-0402"))
    )
    (comp (ref "R30")
      (value "680R")
      (footprint "eagle-import:R0402")
      (libsource (lib "eagle-import") (part "R-0402"))
    )
    (comp (ref "R31")
      (value "680R")
      (footprint "eagle-import:R0402")
      (libsource (lib "eagle-import") (part "R-0402"))
    )
    (comp (ref "R32")
      (value "680R")
      (footprint "eagle-import:R0402")
      (libsource (lib "eagle-import") (part "R-0402"))
    )
    (comp (ref "R33")
      (value "10k")
      (footprint "eagle-import:R0402")
      (libsource (lib "eagle-import") (part "R-0402"))
    )
    (comp (ref "R34")
      (value "10k")
      (footprint "eagle-import:R0402")
      (libsource (lib "eagle-import") (part "R-0402"))
    )
    (comp (ref "R35")
      (value "DNP")
      (footprint "eagle-import:R0603")
      (libsource (lib "eagle-import") (part "RES-0603"))
    )
    (comp (ref "R36")
      (value "0R")
      (footprint "eagle-import:R0402")
      (libsource (lib "eagle-import") (part "R-0402"))
    )
    (comp (ref "R37")
      (value "220R")
      (footprint "eagle-import:R0402")
      (libsource (lib "eagle-import") (part "R-0402"))
    )
    (comp (ref "R38")
      (value "10k")
      (footprint "eagle-import:R0402")
      (libsource (lib "eagle-import") (part "R-0402"))
    )
    (comp (ref "R39")
      (value "100R")
      (footprint "eagle-import:R0402")
      (libsource (lib "eagle-import") (part "R-0402"))
    )
    (comp (ref "R40")
      (value "100R")
      (footprint "eagle-import:R0402")
      (libsource (lib "eagle-import") (part "R-0402"))
    )
    (comp (ref "R41")
      (value "100R")
      (footprint "eagle-import:R0402")
      (libsource (lib "eagle-import") (part "R-0402"))
    )
    (comp (ref "R42")
      (value "10k")
      (footprint "eagle-import:R0402")
      (libsource (lib "eagle-import") (part "R-0402"))
    )
    (comp (ref "R43")
      (value "DNP")
      (footprint "eagle-import:R0402")
      (libsource (lib "eagle-import") (part "R-0402"))
    )
    (comp (ref "R44")
      (value "DNP")
      (footprint "eagle-import:R0402")
      (libsource (lib "eagle-import") (part "R-0402"))
    )
    (comp (ref "R45")
      (value "0R")
      (footprint "eagle-import:R0402")
      (libsource (lib "eagle-import") (part "R-0402"))
    )
    (comp (ref "R46")
      (value "DNP")
      (footprint "eagle-import:R0402")
      (libsource (lib "eagle-import") (part "R-0402"))
    )
    (comp (ref "R47")
      (value "1k")
      (footprint "eagle-import:R0402")
      (libsource (lib "eagle-import") (part "R-0402"))
    )
    (comp (ref "R48")
      (value "0R")
      (footprint "eagle-import:R0402")
      (libsource (lib "eagle-import") (part "R-0402"))
    )
    (comp (ref "R49")
      (value "DNP")
      (footprint "eagle-import:R0402")
      (libsource (lib "eagle-import") (part "R-0402"))
    )
    (comp (ref "R50")
      (value "0R")
      (footprint "eagle-import:R0402")
      (libsource (lib "eagle-import") (part "R-0402"))
    )
    (comp (ref "R51")
      (value "DNP")
      (footprint "eagle-import:R0402")
      (libsource (lib "eagle-import") (part "R-0402"))
    )
    (comp (ref "R52")
      (value "DNP")
      (footprint "eagle-import:R0603")
      (libsource (lib "eagle-import") (part "RES-0603"))
    )
    (comp (ref "R53")
      (value "0R")
      (footprint "eagle-import:R0402")
      (libsource (lib "eagle-import") (part "R-0402"))
    )
    (comp (ref "R54")
      (value "0R")
      (footprint "eagle-import:R0402")
      (libsource (lib "eagle-import") (part "R-0402"))
    )
    (comp (ref "R55")
      (value "DNP")
      (footprint "eagle-import:R0402")
      (libsource (lib "eagle-import") (part "R-0402"))
    )
    (comp (ref "R56")
      (value "DNP")
      (footprint "eagle-import:R0402")
      (libsource (lib "eagle-import") (part "R-0402"))
    )
    (comp (ref "R57")
      (value "10k")
      (footprint "eagle-import:R0402")
      (libsource (lib "eagle-import") (part "R-0402"))
    )
    (comp (ref "R58")
      (value "4.7k")
      (footprint "eagle-import:R0402")
      (libsource (lib "eagle-import") (part "R-0402"))
    )
    (comp (ref "R59")
      (value "DNP")
      (footprint "eagle-import:R0402")
      (libsource (lib "eagle-import") (part "R-0402"))
    )
    (comp (ref "R60")
      (value "DNP")
      (footprint "eagle-import:R0402")
      (libsource (lib "eagle-import") (part "R-0402"))
    )
    (comp (ref "R61")
      (value "DNP")
      (footprint "eagle-import:R0402")
      (libsource (lib "eagle-import") (part "R-0402"))
    )
    (comp (ref "R62")
      (value "DNP")
      (footprint "eagle-import:R0402")
      (libsource (lib "eagle-import") (part "R-0402"))
    )
    (comp (ref "R63")
      (value "DNP")
      (footprint "eagle-import:R0402")
      (libsource (lib "eagle-import") (part "R-0402"))
    )
    (comp (ref "R64")
      (value "22R")
      (footprint "eagle-import:R0402")
      (libsource (lib "eagle-import") (part "R-0402"))
    )
    (comp (ref "R65")
      (value "10k")
      (footprint "eagle-import:R0402")
      (libsource (lib "eagle-import") (part "R-0402"))
    )
    (comp (ref "R66")
      (value "22R")
      (footprint "eagle-import:R0402")
      (libsource (lib "eagle-import") (part "R-0402"))
    )
    (comp (ref "R67")
      (value "DNP")
      (footprint "eagle-import:R0402")
      (libsource (lib "eagle-import") (part "R-0402"))
    )
    (comp (ref "R68")
      (value "4.7k")
      (footprint "eagle-import:R0402")
      (libsource (lib "eagle-import") (part "R-0402"))
    )
    (comp (ref "R69")
      (value "0R")
      (footprint "eagle-import:R0402")
      (libsource (lib "eagle-import") (part "R-0402"))
    )
    (comp (ref "R70")
      (value "DNP")
      (footprint "eagle-import:R0402")
      (libsource (lib "eagle-import") (part "R-0402"))
    )
    (comp (ref "R71")
      (value "10k")
      (footprint "eagle-import:R0402")
      (libsource (lib "eagle-import") (part "R-0402"))
    )
    (comp (ref "R72")
      (value "DNP")
      (footprint "eagle-import:R0402")
      (libsource (lib "eagle-import") (part "R-0402"))
    )
    (comp (ref "R73")
      (value "DNP")
      (footprint "eagle-import:R0402")
      (libsource (lib "eagle-import") (part "R-0402"))
    )
    (comp (ref "R74")
      (value "DNP")
      (footprint "eagle-import:R0402")
      (libsource (lib "eagle-import") (part "R-0402"))
    )
    (comp (ref "R75")
      (value "DNP")
      (footprint "eagle-import:R0402")
      (libsource (lib "eagle-import") (part "R-0402"))
    )
    (comp (ref "R76")
      (value "DNP")
      (footprint "eagle-import:R0402")
      (libsource (lib "eagle-import") (part "R-0402"))
    )
    (comp (ref "R77")
      (value "0R")
      (footprint "eagle-import:R0402")
      (libsource (lib "eagle-import") (part "R-0402"))
    )
    (comp (ref "R78")
      (value "100k")
      (footprint "eagle-import:R0402")
      (libsource (lib "eagle-import") (part "R-0402"))
    )
    (comp (ref "R79")
      (value "1k")
      (footprint "eagle-import:R0402")
      (libsource (lib "eagle-import") (part "R-0402"))
    )
    (comp (ref "R80")
      (value "10R")
      (footprint "eagle-import:R0402")
      (libsource (lib "eagle-import") (part "R-0402"))
    )
    (comp (ref "R81")
      (value "DNP")
      (footprint "eagle-import:R0402")
      (libsource (lib "eagle-import") (part "R-0402"))
    )
    (comp (ref "R82")
      (value "100k")
      (footprint "eagle-import:R0402")
      (libsource (lib "eagle-import") (part "R-0402"))
    )
    (comp (ref "R83")
      (value "200k_1%")
      (footprint "eagle-import:R0402")
      (libsource (lib "eagle-import") (part "R-0402"))
    )
    (comp (ref "R87")
      (value "200k_1%")
      (footprint "eagle-import:R0402")
      (libsource (lib "eagle-import") (part "R-0402"))
    )
    (comp (ref "S1")
      (value "323030226")
      (footprint "eagle-import:SHIELD_CLIP")
      (libsource (lib "eagle-import") (part "SHIELD_CLIP"))
    )
    (comp (ref "S2")
      (value "323030226")
      (footprint "eagle-import:SHIELD_CLIP")
      (libsource (lib "eagle-import") (part "SHIELD_CLIP"))
    )
    (comp (ref "S3")
      (value "323030226")
      (footprint "eagle-import:SHIELD_CLIP")
      (libsource (lib "eagle-import") (part "SHIELD_CLIP"))
    )
    (comp (ref "S4")
      (value "323030226")
      (footprint "eagle-import:SHIELD_CLIP")
      (libsource (lib "eagle-import") (part "SHIELD_CLIP"))
    )
    (comp (ref "S5")
      (value "323030226")
      (footprint "eagle-import:SHIELD_CLIP")
      (libsource (lib "eagle-import") (part "SHIELD_CLIP"))
    )
    (comp (ref "S6")
      (value "323030226")
      (footprint "eagle-import:SHIELD_CLIP")
      (libsource (lib "eagle-import") (part "SHIELD_CLIP"))
    )
    (comp (ref "TP1")
      (value "TEST-POINT-35")
      (footprint "eagle-import:TP_3535")
      (libsource (lib "eagle-import") (part "TEST-POINT-35"))
    )
    (comp (ref "TP2")
      (value "TEST-POINT-35")
      (footprint "eagle-import:TP_3535")
      (libsource (lib "eagle-import") (part "TEST-POINT-35"))
    )
    (comp (ref "TP3")
      (value "TEST-POINT-35")
      (footprint "eagle-import:TP_3535")
      (libsource (lib "eagle-import") (part "TEST-POINT-35"))
    )
    (comp (ref "TP4")
      (value "TEST-POINT-35")
      (footprint "eagle-import:TP_3535")
      (libsource (lib "eagle-import") (part "TEST-POINT-35"))
    )
    (comp (ref "TP5")
      (value "TEST-POINT-35")
      (footprint "eagle-import:TP_3535")
      (libsource (lib "eagle-import") (part "TEST-POINT-35"))
    )
    (comp (ref "TP6")
      (value "TEST-POINT-35")
      (footprint "eagle-import:TP_3535")
      (libsource (lib "eagle-import") (part "TEST-POINT-35"))
    )
    (comp (ref "TP7")
      (value "TEST-POINT-35")
      (footprint "eagle-import:TP_3535")
      (libsource (lib "eagle-import") (part "TEST-POINT-35"))
    )
    (comp (ref "TP8")
      (value "TEST-POINT-35")
      (footprint "eagle-import:TP_3535")
      (libsource (lib "eagle-import") (part "TEST-POINT-35"))
    )
    (comp (ref "TP9")
      (value "TEST-POINT-35")
      (footprint "eagle-import:TP_3535")
      (libsource (lib "eagle-import") (part "TEST-POINT-35"))
    )
    (comp (ref "TP10")
      (value "TEST-POINT-35")
      (footprint "eagle-import:TP_3535")
      (libsource (lib "eagle-import") (part "TEST-POINT-35"))
    )
    (comp (ref "TP14")
      (value "TEST-POINT-35")
      (footprint "eagle-import:TP_3535")
      (libsource (lib "eagle-import") (part "TEST-POINT-35"))
    )
    (comp (ref "TP15")
      (value "TEST-POINT'4545'")
      (footprint "eagle-import:TP-D45MIL")
      (fields (field (name "PARTNO") "DNP"))
      (libsource (lib "eagle-import") (part "TEST-POINT'4545'"))
    )
    (comp (ref "U1")
      (value "SX1302IMLTRT")
      (footprint "eagle-import:QFN68-0.35-7X7X0.75MM")
      (libsource (lib "eagle-import") (part "TRANSCEIVER-SX1302"))
    )
    (comp (ref "U2")
      (value "HDF866A3-S6")
      (footprint "eagle-import:FILTER6P-1.1-3X3X1.3MM")
      (libsource (lib "eagle-import") (part "FILTER-B39871B3717U410"))
    )
    (comp (ref "U3")
      (value "DNP")
      (footprint "eagle-import:SOT-23-5")
      (libsource (lib "eagle-import") (part "LDO-XC6227C331MR"))
    )
    (comp (ref "U4")
      (value "DNP")
      (footprint "eagle-import:SOT-23-5")
      (libsource (lib "eagle-import") (part "LDO-XC6227C331MR"))
    )
    (comp (ref "U5")
      (value "SX1250IMLTRT")
      (footprint "eagle-import:QFN24G-0.5-4X4MM")
      (libsource (lib "eagle-import") (part "RF-SX1250"))
    )
    (comp (ref "U6")
      (value "MP2161GJ")
      (footprint "eagle-import:TSOT23-8")
      (libsource (lib "eagle-import") (part "PMIC-MP2161'GJ'"))
    )
    (comp (ref "U7")
      (value "SX1250IMLTRT")
      (footprint "eagle-import:QFN24G-0.5-4X4MM")
      (libsource (lib "eagle-import") (part "RF-SX1250"))
    )
    (comp (ref "U8")
      (value "HDF866A3-S6")
      (footprint "eagle-import:FILTER6P-1.1-3X3X1.3MM")
      (libsource (lib "eagle-import") (part "FILTER-B39871B3717U410"))
    )
    (comp (ref "U9")
      (value "SKY66420-11")
      (footprint "eagle-import:MODULE16P-0.5-3X3X0.75MM")
      (libsource (lib "eagle-import") (part "MODULE-RF-SKY66420-11"))
    )
    (comp (ref "U10")
      (value "HDF866A3-S6")
      (footprint "eagle-import:FILTER6P-1.1-3X3X1.3MM")
      (libsource (lib "eagle-import") (part "FILTER-B39871B3717U410"))
    )
    (comp (ref "U11")
      (value "SX1262IMLTRT")
      (footprint "eagle-import:QFN24G-0.5-4X4MM")
      (libsource (lib "eagle-import") (part "TRANSCEIVER-SX1261/2"))
    )
    (comp (ref "U12")
      (value "STM32L412K8U6")
      (footprint "eagle-import:UFQFPN32-0.5-5X5MM")
      (libsource (lib "eagle-import") (part "MCU-STM32L412KXU6"))
    )
    (comp (ref "U13")
      (value "STTS751")
      (footprint "eagle-import:UDFN-6L")
      (libsource (lib "eagle-import") (part "SENSOR-STTS751"))
    )
    (comp (ref "X1")
      (value "DSB221SDN")
      (footprint "eagle-import:X4-SMD-2.5X2.0X1.0MM")
      (libsource (lib "eagle-import") (part "CRYSTAL-OSCILLATOR-2520"))
    )
    (comp (ref "X3")
      (value "32.768kHz")
      (footprint "eagle-import:X2-SMD-3.2X1.5X0.55MM")
      (libsource (lib "eagle-import") (part "CRYSTAL-2P-3215"))
    )
  )
  (nets
    (net (code "1") (name "32MHZ") (class "Default")
      (node (ref "R37") (pin "2") (pinfunction "2_2") (pintype "passive"))
      (node (ref "R6") (pin "2") (pinfunction "2_2") (pintype "passive"))
      (node (ref "R9") (pin "2") (pinfunction "2_2") (pintype "passive"))
      (node (ref "X1") (pin "3") (pinfunction "OUT_3") (pintype "bidirectional"))
    )
    (net (code "2") (name "1302_CS") (class "Default")
      (node (ref "R33") (pin "2") (pinfunction "2_2") (pintype "passive"))
      (node (ref "R43") (pin "1") (pinfunction "1_1") (pintype "passive"))
      (node (ref "U1") (pin "1") (pinfunction "HOST_CSN_1") (pintype "bidirectional"))
      (node (ref "U12") (pin "10") (pinfunction "PA4_10") (pintype "bidirectional"))
    )
    (net (code "3") (name "1302_RESET") (class "Default")
      (node (ref "C1") (pin "2") (pinfunction "2_2") (pintype "passive"))
      (node (ref "D7") (pin "-") (pinfunction "-_-") (pintype "passive"))
      (node (ref "R1") (pin "2") (pinfunction "2_2") (pintype "passive"))
      (node (ref "U1") (pin "7") (pinfunction "RESET_7") (pintype "bidirectional"))
      (node (ref "U12") (pin "8") (pinfunction "PA2_8") (pintype "bidirectional"))
    )
    (net (code "4") (name "1302_RESET_HOST") (class "Default")
      (node (ref "D7") (pin "+") (pinfunction "+_+") (pintype "passive"))
      (node (ref "R59") (pin "1") (pinfunction "1_1") (pintype "passive"))
    )
    (net (code "5") (name "CONFIG_OK") (class "Default")
      (node (ref "R31") (pin "1") (pinfunction "1_1") (pintype "passive"))
      (node (ref "U1") (pin "66") (pinfunction "GPIO0_66") (pintype "bidirectional"))
    )
    (net (code "6") (name "DM") (class "Default")
      (node (ref "J1") (pin "36") (pinfunction "36_36") (pintype "bidirectional"))
      (node (ref "R66") (pin "1") (pinfunction "1_1") (pintype "passive"))
    )
    (net (code "7") (name "DP") (class "Default")
      (node (ref "J1") (pin "38") (pinfunction "38_38") (pintype "bidirectional"))
      (node (ref "R64") (pin "1") (pinfunction "1_1") (pintype "passive"))
    )
    (net (code "8") (name "FEM_CS") (class "Default")
      (node (ref "R14") (pin "2") (pinfunction "2_2") (pintype "passive"))
      (node (ref "R34") (pin "1") (pinfunction "1_1") (pintype "passive"))
      (node (ref "U1") (pin "10") (pinfunction "RADIO_CTRL0_10") (pintype "bidirectional"))
      (node (ref "U3") (pin "3") (pinfunction "CE_3") (pintype "bidirectional"))
    )
    (net (code "9") (name "FEM_PA_ON") (class "Default")
      (node (ref "R15") (pin "2") (pinfunction "2_2") (pintype "passive"))
      (node (ref "U1") (pin "16") (pinfunction "RADIO_CTRL4_16") (pintype "bidirectional"))
    )
    (net (code "10") (name "GND_POWER") (class "Default")
      (node (ref "ANT1") (pin "GND1") (pinfunction "GND1_GND1") (pintype "bidirectional"))
      (node (ref "ANT1") (pin "GND2") (pinfunction "GND2_GND2") (pintype "bidirectional"))
      (node (ref "ANT2") (pin "GND1") (pinfunction "GND1_GND1") (pintype "bidirectional"))
      (node (ref "ANT2") (pin "GND2") (pinfunction "GND2_GND2") (pintype "bidirectional"))
      (node (ref "C12") (pin "1") (pinfunction "1_1") (pintype "passive"))
      (node (ref "C13") (pin "1") (pinfunction "1_1") (pintype "passive"))
      (node (ref "C15") (pin "1") (pinfunction "1_1") (pintype "passive"))
      (node (ref "C16") (pin "1") (pinfunction "1_1") (pintype "passive"))
      (node (ref "C17") (pin "1") (pinfunction "1_1") (pintype "passive"))
      (node (ref "C18") (pin "1") (pinfunction "1_1") (pintype "passive"))
      (node (ref "C19") (pin "1") (pinfunction "1_1") (pintype "passive"))
      (node (ref "C2") (pin "1") (pinfunction "1_1") (pintype "passive"))
      (node (ref "C20") (pin "1") (pinfunction "1_1") (pintype "passive"))
      (node (ref "C21") (pin "1") (pinfunction "1_1") (pintype "passive"))
      (node (ref "C22") (pin "1") (pinfunction "1_1") (pintype "passive"))
      (node (ref "C23") (pin "1") (pinfunction "1_1") (pintype "passive"))
      (node (ref "C24") (pin "1") (pinfunction "1_1") (pintype "passive"))
      (node (ref "C25") (pin "1") (pinfunction "1_1") (pintype "passive"))
      (node (ref "C26") (pin "1") (pinfunction "1_1") (pintype "passive"))
      (node (ref "C27") (pin "1") (pinfunction "1_1") (pintype "passive"))
      (node (ref "C28") (pin "1") (pinfunction "1_1") (pintype "passive"))
      (node (ref "C29") (pin "1") (pinfunction "1_1") (pintype "passive"))
      (node (ref "C3") (pin "1") (pinfunction "1_1") (pintype "passive"))
      (node (ref "C30") (pin "1") (pinfunction "1_1") (pintype "passive"))
      (node (ref "C31") (pin "1") (pinfunction "1_1") (pintype "passive"))
      (node (ref "C32") (pin "1") (pinfunction "1_1") (pintype "passive"))
      (node (ref "C33") (pin "1") (pinfunction "1_1") (pintype "passive"))
      (node (ref "C34") (pin "1") (pinfunction "1_1") (pintype "passive"))
      (node (ref "C35") (pin "1") (pinfunction "1_1") (pintype "passive"))
      (node (ref "C36") (pin "1") (pinfunction "1_1") (pintype "passive"))
      (node (ref "C37") (pin "1") (pinfunction "1_1") (pintype "passive"))
      (node (ref "C39") (pin "1") (pinfunction "1_1") (pintype "passive"))
      (node (ref "C40") (pin "1") (pinfunction "1_1") (pintype "passive"))
      (node (ref "C41") (pin "1") (pinfunction "1_1") (pintype "passive"))
      (node (ref "C42") (pin "1") (pinfunction "1_1") (pintype "passive"))
      (node (ref "C43") (pin "1") (pinfunction "1_1") (pintype "passive"))
      (node (ref "C44") (pin "1") (pinfunction "1_1") (pintype "passive"))
      (node (ref "C45") (pin "1") (pinfunction "1_1") (pintype "passive"))
      (node (ref "C46") (pin "1") (pinfunction "1_1") (pintype "passive"))
      (node (ref "C47") (pin "1") (pinfunction "1_1") (pintype "passive"))
      (node (ref "C48") (pin "1") (pinfunction "1_1") (pintype "passive"))
      (node (ref "C49") (pin "1") (pinfunction "1_1") (pintype "passive"))
      (node (ref "C5") (pin "1") (pinfunction "1_1") (pintype "passive"))
      (node (ref "C50") (pin "1") (pinfunction "1_1") (pintype "passive"))
      (node (ref "C51") (pin "1") (pinfunction "1_1") (pintype "passive"))
      (node (ref "C52") (pin "1") (pinfunction "1_1") (pintype "passive"))
      (node (ref "C55") (pin "1") (pinfunction "1_1") (pintype "passive"))
      (node (ref "C56") (pin "1") (pinfunction "1_1") (pintype "passive"))
      (node (ref "C57") (pin "1") (pinfunction "1_1") (pintype "passive"))
      (node (ref "C58") (pin "1") (pinfunction "1_1") (pintype "passive"))
      (node (ref "C60") (pin "2") (pinfunction "2_2") (pintype "passive"))
      (node (ref "C61") (pin "2") (pinfunction "2_2") (pintype "passive"))
      (node (ref "C62") (pin "1") (pinfunction "1_1") (pintype "passive"))
      (node (ref "C63") (pin "2") (pinfunction "2_2") (pintype "passive"))
      (node (ref "C65") (pin "2") (pinfunction "2_2") (pintype "passive"))
      (node (ref "C67") (pin "2") (pinfunction "2_2") (pintype "passive"))
      (node (ref "C69") (pin "1") (pinfunction "1_1") (pintype "passive"))
      (node (ref "C7") (pin "1") (pinfunction "1_1") (pintype "passive"))
      (node (ref "C70") (pin "1") (pinfunction "1_1") (pintype "passive"))
      (node (ref "C71") (pin "1") (pinfunction "1_1") (pintype "passive"))
      (node (ref "C72") (pin "1") (pinfunction "1_1") (pintype "passive"))
      (node (ref "C73") (pin "2") (pinfunction "2_2") (pintype "passive"))
      (node (ref "C74") (pin "2") (pinfunction "2_2") (pintype "passive"))
      (node (ref "C76") (pin "1") (pinfunction "1_1") (pintype "passive"))
      (node (ref "C77") (pin "2") (pinfunction "2_2") (pintype "passive"))
      (node (ref "C78") (pin "2") (pinfunction "2_2") (pintype "passive"))
      (node (ref "C80") (pin "1") (pinfunction "1_1") (pintype "passive"))
      (node (ref "C81") (pin "2") (pinfunction "2_2") (pintype "passive"))
      (node (ref "C82") (pin "2") (pinfunction "2_2") (pintype "passive"))
      (node (ref "C83") (pin "1") (pinfunction "1_1") (pintype "passive"))
      (node (ref "C84") (pin "2") (pinfunction "2_2") (pintype "passive"))
      (node (ref "C85") (pin "1") (pinfunction "1_1") (pintype "passive"))
      (node (ref "C86") (pin "1") (pinfunction "1_1") (pintype "passive"))
      (node (ref "C87") (pin "1") (pinfunction "1_1") (pintype "passive"))
      (node (ref "C88") (pin "1") (pinfunction "1_1") (pintype "passive"))
      (node (ref "C89") (pin "1") (pinfunction "1_1") (pintype "passive"))
      (node (ref "C9") (pin "1") (pinfunction "1_1") (pintype "passive"))
      (node (ref "C90") (pin "1") (pinfunction "1_1") (pintype "passive"))
      (node (ref "C92") (pin "1") (pinfunction "1_1") (pintype "passive"))
      (node (ref "D1") (pin "-") (pinfunction "-_-") (pintype "passive"))
      (node (ref "D2") (pin "-") (pinfunction "-_-") (pintype "passive"))
      (node (ref "D3") (pin "-") (pinfunction "-_-") (pintype "passive"))
      (node (ref "D4") (pin "-") (pinfunction "-_-") (pintype "passive"))
      (node (ref "D5") (pin "1") (pinfunction "1_1") (pintype "bidirectional"))
      (node (ref "D6") (pin "1") (pinfunction "1_1") (pintype "bidirectional"))
      (node (ref "J1") (pin "15") (pinfunction "GND_15") (pintype "bidirectional"))
      (node (ref "J1") (pin "18") (pinfunction "GND_18") (pintype "bidirectional"))
      (node (ref "J1") (pin "21") (pinfunction "GND_21") (pintype "bidirectional"))
      (node (ref "J1") (pin "26") (pinfunction "GND_26") (pintype "bidirectional"))
      (node (ref "J1") (pin "27") (pinfunction "GND_27") (pintype "bidirectional"))
      (node (ref "J1") (pin "29") (pinfunction "GND_29") (pintype "bidirectional"))
      (node (ref "J1") (pin "34") (pinfunction "GND_34") (pintype "bidirectional"))
      (node (ref "J1") (pin "35") (pinfunction "GND_35") (pintype "bidirectional"))
      (node (ref "J1") (pin "37") (pinfunction "GND_37") (pintype "bidirectional"))
      (node (ref "J1") (pin "4") (pinfunction "GND_4") (pintype "bidirectional"))
      (node (ref "J1") (pin "40") (pinfunction "GND_40") (pintype "bidirectional"))
      (node (ref "J1") (pin "43") (pinfunction "GND_43") (pintype "bidirectional"))
      (node (ref "J1") (pin "50") (pinfunction "GND_50") (pintype "bidirectional"))
      (node (ref "J1") (pin "9") (pinfunction "GND_9") (pintype "bidirectional"))
      (node (ref "J1") (pin "S1") (pinfunction "GND_S1") (pintype "bidirectional"))
      (node (ref "J1") (pin "S2") (pinfunction "GND_S2") (pintype "bidirectional"))
      (node (ref "Q10") (pin "2") (pinfunction "S_2") (pintype "passive"))
      (node (ref "R1") (pin "1") (pinfunction "1_1") (pintype "passive"))
      (node (ref "R11") (pin "1") (pinfunction "1_1") (pintype "passive"))
      (node (ref "R12") (pin "1") (pinfunction "1_1") (pintype "passive"))
      (node (ref "R17") (pin "2") (pinfunction "2_2") (pintype "passive"))
      (node (ref "R4") (pin "1") (pinfunction "1_1") (pintype "passive"))
      (node (ref "R53") (pin "1") (pinfunction "1_1") (pintype "passive"))
      (node (ref "R53") (pin "2") (pinfunction "2_2") (pintype "passive"))
      (node (ref "R54") (pin "1") (pinfunction "1_1") (pintype "passive"))
      (node (ref "R54") (pin "2") (pinfunction "2_2") (pintype "passive"))
      (node (ref "R55") (pin "1") (pinfunction "1_1") (pintype "passive"))
      (node (ref "R55") (pin "2") (pinfunction "2_2") (pintype "passive"))
      (node (ref "R57") (pin "2") (pinfunction "2_2") (pintype "passive"))
      (node (ref "R73") (pin "1") (pinfunction "1_1") (pintype "passive"))
      (node (ref "R74") (pin "1") (pinfunction "1_1") (pintype "passive"))
      (node (ref "R74") (pin "2") (pinfunction "2_2") (pintype "passive"))
      (node (ref "R87") (pin "1") (pinfunction "1_1") (pintype "passive"))
      (node (ref "S1") (pin "S1") (pinfunction "S1_S1") (pintype "bidirectional"))
      (node (ref "S1") (pin "S2") (pinfunction "S1_S2") (pintype "bidirectional"))
      (node (ref "S1") (pin "S3") (pinfunction "S1_S3") (pintype "bidirectional"))
      (node (ref "S1") (pin "S4") (pinfunction "S1_S4") (pintype "bidirectional"))
      (node (ref "S1") (pin "S5") (pinfunction "S1_S5") (pintype "bidirectional"))
      (node (ref "S2") (pin "S1") (pinfunction "S1_S1") (pintype "bidirectional"))
      (node (ref "S2") (pin "S2") (pinfunction "S1_S2") (pintype "bidirectional"))
      (node (ref "S2") (pin "S3") (pinfunction "S1_S3") (pintype "bidirectional"))
      (node (ref "S2") (pin "S4") (pinfunction "S1_S4") (pintype "bidirectional"))
      (node (ref "S2") (pin "S5") (pinfunction "S1_S5") (pintype "bidirectional"))
      (node (ref "S3") (pin "S1") (pinfunction "S1_S1") (pintype "bidirectional"))
      (node (ref "S3") (pin "S2") (pinfunction "S1_S2") (pintype "bidirectional"))
      (node (ref "S3") (pin "S3") (pinfunction "S1_S3") (pintype "bidirectional"))
      (node (ref "S3") (pin "S4") (pinfunction "S1_S4") (pintype "bidirectional"))
      (node (ref "S3") (pin "S5") (pinfunction "S1_S5") (pintype "bidirectional"))
      (node (ref "S4") (pin "S1") (pinfunction "S1_S1") (pintype "bidirectional"))
      (node (ref "S4") (pin "S2") (pinfunction "S1_S2") (pintype "bidirectional"))
      (node (ref "S4") (pin "S3") (pinfunction "S1_S3") (pintype "bidirectional"))
      (node (ref "S4") (pin "S4") (pinfunction "S1_S4") (pintype "bidirectional"))
      (node (ref "S4") (pin "S5") (pinfunction "S1_S5") (pintype "bidirectional"))
      (node (ref "S5") (pin "S1") (pinfunction "S1_S1") (pintype "bidirectional"))
      (node (ref "S5") (pin "S2") (pinfunction "S1_S2") (pintype "bidirectional"))
      (node (ref "S5") (pin "S3") (pinfunction "S1_S3") (pintype "bidirectional"))
      (node (ref "S5") (pin "S4") (pinfunction "S1_S4") (pintype "bidirectional"))
      (node (ref "S5") (pin "S5") (pinfunction "S1_S5") (pintype "bidirectional"))
      (node (ref "S6") (pin "S1") (pinfunction "S1_S1") (pintype "bidirectional"))
      (node (ref "S6") (pin "S2") (pinfunction "S1_S2") (pintype "bidirectional"))
      (node (ref "S6") (pin "S3") (pinfunction "S1_S3") (pintype "bidirectional"))
      (node (ref "S6") (pin "S4") (pinfunction "S1_S4") (pintype "bidirectional"))
      (node (ref "S6") (pin "S5") (pinfunction "S1_S5") (pintype "bidirectional"))
      (node (ref "TP3") (pin "T") (pinfunction "T_T") (pintype "bidirectional"))
      (node (ref "U1") (pin "15") (pinfunction "GND_15") (pintype "bidirectional"))
      (node (ref "U1") (pin "24") (pinfunction "GND_24") (pintype "bidirectional"))
      (node (ref "U1") (pin "25") (pinfunction "GND_25") (pintype "bidirectional"))
      (node (ref "U1") (pin "39") (pinfunction "GND_39") (pintype "bidirectional"))
      (node (ref "U1") (pin "46") (pinfunction "GND_46") (pintype "bidirectional"))
      (node (ref "U1") (pin "55") (pinfunction "GND_55") (pintype "bidirectional"))
      (node (ref "U1") (pin "6") (pinfunction "GND_6") (pintype "bidirectional"))
      (node (ref "U1") (pin "62") (pinfunction "GND_62") (pintype "bidirectional"))
      (node (ref "U1") (pin "69") (pinfunction "GND_69") (pintype "bidirectional"))
      (node (ref "U1") (pin "9") (pinfunction "GND_9") (pintype "bidirectional"))
      (node (ref "U10") (pin "1") (pinfunction "GND_1") (pintype "bidirectional"))
      (node (ref "U10") (pin "3") (pinfunction "GND_3") (pintype "bidirectional"))
      (node (ref "U10") (pin "4") (pinfunction "GND_4") (pintype "bidirectional"))
      (node (ref "U10") (pin "6") (pinfunction "GND_6") (pintype "bidirectional"))
      (node (ref "U11") (pin "2") (pinfunction "GND_2") (pintype "bidirectional"))
      (node (ref "U11") (pin "20") (pinfunction "GND_20") (pintype "bidirectional"))
      (node (ref "U11") (pin "5") (pinfunction "GND_5") (pintype "bidirectional"))
      (node (ref "U11") (pin "8") (pinfunction "GND_8") (pintype "bidirectional"))
      (node (ref "U11") (pin "PAD") (pinfunction "PAD_PAD") (pintype "bidirectional"))
      (node (ref "U12") (pin "16") (pinfunction "VSS_16") (pintype "bidirectional"))
      (node (ref "U12") (pin "32") (pinfunction "VSS_32") (pintype "bidirectional"))
      (node (ref "U12") (pin "PAD") (pinfunction "PAD_PAD") (pintype "bidirectional"))
      (node (ref "U13") (pin "4") (pinfunction "ADDR/~{THERM}_4") (pintype "bidirectional"))
      (node (ref "U13") (pin "5") (pinfunction "GND_5") (pintype "bidirectional"))
      (node (ref "U2") (pin "1") (pinfunction "GND_1") (pintype "bidirectional"))
      (node (ref "U2") (pin "3") (pinfunction "GND_3") (pintype "bidirectional"))
      (node (ref "U2") (pin "4") (pinfunction "GND_4") (pintype "bidirectional"))
      (node (ref "U2") (pin "6") (pinfunction "GND_6") (pintype "bidirectional"))
      (node (ref "U3") (pin "2") (pinfunction "VSS_2") (pintype "bidirectional"))
      (node (ref "U4") (pin "2") (pinfunction "VSS_2") (pintype "bidirectional"))
      (node (ref "U5") (pin "20") (pinfunction "GND_20") (pintype "bidirectional"))
      (node (ref "U5") (pin "7") (pinfunction "GND_7") (pintype "bidirectional"))
      (node (ref "U5") (pin "PAD") (pinfunction "PAD_PAD") (pintype "bidirectional"))
      (node (ref "U6") (pin "4") (pinfunction "PGND_4") (pintype "bidirectional"))
      (node (ref "U6") (pin "6") (pinfunction "AGND_6") (pintype "bidirectional"))
      (node (ref "U7") (pin "20") (pinfunction "GND_20") (pintype "bidirectional"))
      (node (ref "U7") (pin "7") (pinfunction "GND_7") (pintype "bidirectional"))
      (node (ref "U7") (pin "PAD") (pinfunction "PAD_PAD") (pintype "bidirectional"))
      (node (ref "U8") (pin "1") (pinfunction "GND_1") (pintype "bidirectional"))
      (node (ref "U8") (pin "3") (pinfunction "GND_3") (pintype "bidirectional"))
      (node (ref "U8") (pin "4") (pinfunction "GND_4") (pintype "bidirectional"))
      (node (ref "U8") (pin "6") (pinfunction "GND_6") (pintype "bidirectional"))
      (node (ref "U9") (pin "10") (pinfunction "GND_10") (pintype "bidirectional"))
      (node (ref "U9") (pin "12") (pinfunction "GND_12") (pintype "bidirectional"))
      (node (ref "U9") (pin "17") (pinfunction "EPAD_17") (pintype "bidirectional"))
      (node (ref "X1") (pin "2") (pinfunction "GND_2") (pintype "bidirectional"))
    )
    (net (code "11") (name "HOST_CS0") (class "Default")
      (node (ref "J1") (pin "51") (pinfunction "51_51") (pintype "bidirectional"))
      (node (ref "R43") (pin "2") (pinfunction "2_2") (pintype "passive"))
    )
    (net (code "12") (name "HOST_CS1") (class "Default")
      (node (ref "J1") (pin "25") (pinfunction "25_25") (pintype "bidirectional"))
      (node (ref "R51") (pin "2") (pinfunction "2_2") (pintype "passive"))
    )
    (net (code "13") (name "HOST_IO1") (class "Default")
      (node (ref "J1") (pin "33") (pinfunction "33_33") (pintype "bidirectional"))
      (node (ref "R61") (pin "2") (pinfunction "2_2") (pintype "passive"))
    )
    (net (code "14") (name "HOST_IO2") (class "Default")
      (node (ref "J1") (pin "31") (pinfunction "31_31") (pintype "bidirectional"))
      (node (ref "R63") (pin "2") (pinfunction "2_2") (pintype "passive"))
    )
    (net (code "15") (name "HOST_IO3") (class "Default")
      (node (ref "J1") (pin "23") (pinfunction "23_23") (pintype "bidirectional"))
    )
    (net (code "16") (name "HOST_IO4") (class "Default")
      (node (ref "J1") (pin "8") (pinfunction "8_8") (pintype "bidirectional"))
      (node (ref "R67") (pin "2") (pinfunction "2_2") (pintype "passive"))
    )
    (net (code "17") (name "HOST_IO5") (class "Default")
      (node (ref "J1") (pin "10") (pinfunction "10_10") (pintype "bidirectional"))
      (node (ref "R60") (pin "2") (pinfunction "2_2") (pintype "passive"))
    )
    (net (code "18") (name "HOST_IO6") (class "Default")
      (node (ref "J1") (pin "12") (pinfunction "12_12") (pintype "bidirectional"))
    )
    (net (code "19") (name "HOST_MISO") (class "Default")
      (node (ref "R39") (pin "1") (pinfunction "1_1") (pintype "passive"))
      (node (ref "R44") (pin "2") (pinfunction "2_2") (pintype "passive"))
    )
    (net (code "20") (name "HOST_MOSI") (class "Default")
      (node (ref "J1") (pin "49") (pinfunction "49_49") (pintype "bidirectional"))
      (node (ref "R46") (pin "2") (pinfunction "2_2") (pintype "passive"))
    )
    (net (code "21") (name "HOST_RST") (class "Default")
      (node (ref "J1") (pin "22") (pinfunction "22_22") (pintype "bidirectional"))
      (node (ref "R59") (pin "2") (pinfunction "2_2") (pintype "passive"))
      (node (ref "R77") (pin "2") (pinfunction "2_2") (pintype "passive"))
    )
    (net (code "22") (name "HOST_SCK") (class "Default")
      (node (ref "J1") (pin "45") (pinfunction "45_45") (pintype "bidirectional"))
      (node (ref "R49") (pin "2") (pinfunction "2_2") (pintype "passive"))
    )
    (net (code "23") (name "I2C_SCL") (class "Default")
      (node (ref "R68") (pin "2") (pinfunction "2_2") (pintype "passive"))
      (node (ref "R76") (pin "1") (pinfunction "1_1") (pintype "passive"))
      (node (ref "R81") (pin "1") (pinfunction "1_1") (pintype "passive"))
      (node (ref "U12") (pin "29") (pinfunction "PB6_29") (pintype "bidirectional"))
      (node (ref "U13") (pin "1") (pinfunction "SCL_1") (pintype "bidirectional"))
    )
    (net (code "24") (name "I2C_SDA") (class "Default")
      (node (ref "R58") (pin "2") (pinfunction "2_2") (pintype "passive"))
      (node (ref "R70") (pin "1") (pinfunction "1_1") (pintype "passive"))
      (node (ref "R75") (pin "1") (pinfunction "1_1") (pintype "passive"))
      (node (ref "U12") (pin "30") (pinfunction "PB7_30") (pintype "bidirectional"))
      (node (ref "U13") (pin "6") (pinfunction "SDA_6") (pintype "bidirectional"))
    )
    (net (code "25") (name "MCU_RESET") (class "Default")
      (node (ref "C85") (pin "2") (pinfunction "2_2") (pintype "passive"))
      (node (ref "R71") (pin "2") (pinfunction "2_2") (pintype "passive"))
      (node (ref "R77") (pin "1") (pinfunction "1_1") (pintype "passive"))
      (node (ref "TP5") (pin "T") (pinfunction "T_T") (pintype "bidirectional"))
      (node (ref "U12") (pin "4") (pinfunction "NRST_4") (pintype "bidirectional"))
    )
    (net (code "26") (name "MISO") (class "Default")
      (node (ref "R44") (pin "1") (pinfunction "1_1") (pintype "passive"))
      (node (ref "R45") (pin "1") (pinfunction "1_1") (pintype "passive"))
      (node (ref "U1") (pin "2") (pinfunction "HOST_MISO_2") (pintype "bidirectional"))
      (node (ref "U11") (pin "16") (pinfunction "MISO_16") (pintype "bidirectional"))
    )
    (net (code "27") (name "MISO_A") (class "Default")
      (node (ref "U1") (pin "42") (pinfunction "RADIO_A_MISO_42") (pintype "bidirectional"))
      (node (ref "U5") (pin "16") (pinfunction "MISO_16") (pintype "bidirectional"))
    )
    (net (code "28") (name "MISO_B") (class "Default")
      (node (ref "U1") (pin "33") (pinfunction "RADIO_B_MISO_33") (pintype "bidirectional"))
      (node (ref "U7") (pin "16") (pinfunction "MISO_16") (pintype "bidirectional"))
    )
    (net (code "29") (name "MOSI") (class "Default")
      (node (ref "R40") (pin "2") (pinfunction "2_2") (pintype "passive"))
      (node (ref "R46") (pin "1") (pinfunction "1_1") (pintype "passive"))
      (node (ref "R48") (pin "1") (pinfunction "1_1") (pintype "passive"))
      (node (ref "R5") (pin "2") (pinfunction "2_2") (pintype "passive"))
    )
    (net (code "30") (name "MOSI_A") (class "Default")
      (node (ref "U1") (pin "67") (pinfunction "RADIO_A_MOSI_67") (pintype "bidirectional"))
      (node (ref "U5") (pin "17") (pinfunction "MOSI_17") (pintype "bidirectional"))
    )
    (net (code "31") (name "MOSI_B") (class "Default")
      (node (ref "U1") (pin "19") (pinfunction "RADIO_B_MOSI_19") (pintype "bidirectional"))
      (node (ref "U7") (pin "17") (pinfunction "MOSI_17") (pintype "bidirectional"))
    )
    (net (code "32") (name "Net-(ANT1-PadD)") (class "Default")
      (node (ref "ANT1") (pin "D") (pinfunction "D_D") (pintype "bidirectional"))
      (node (ref "C64") (pin "2") (pinfunction "2_2") (pintype "passive"))
      (node (ref "D5") (pin "2") (pinfunction "2_2") (pintype "bidirectional"))
    )
    (net (code "33") (name "Net-(ANT2-PadD)") (class "Default")
      (node (ref "ANT2") (pin "D") (pinfunction "D_D") (pintype "bidirectional"))
      (node (ref "C79") (pin "2") (pinfunction "2_2") (pintype "passive"))
      (node (ref "D6") (pin "2") (pinfunction "2_2") (pintype "bidirectional"))
    )
    (net (code "34") (name "Net-(C1-Pad1)") (class "Default")
      (node (ref "C1") (pin "1") (pinfunction "1_1") (pintype "passive"))
      (node (ref "R80") (pin "1") (pinfunction "1_1") (pintype "passive"))
    )
    (net (code "35") (name "Net-(C4-Pad1)") (class "Default")
      (node (ref "C4") (pin "1") (pinfunction "1_1") (pintype "passive"))
      (node (ref "C8") (pin "2") (pinfunction "2_2") (pintype "passive"))
      (node (ref "R12") (pin "2") (pinfunction "2_2") (pintype "passive"))
    )
    (net (code "36") (name "Net-(C14-Pad2)") (class "Default")
      (node (ref "C14") (pin "2") (pinfunction "2_2") (pintype "passive"))
      (node (ref "R6") (pin "1") (pinfunction "1_1") (pintype "passive"))
    )
    (net (code "37") (name "Net-(C38-Pad2)") (class "Default")
      (node (ref "C38") (pin "2") (pinfunction "2_2") (pintype "passive"))
      (node (ref "R9") (pin "1") (pinfunction "1_1") (pintype "passive"))
    )
    (net (code "38") (name "Net-(C53-Pad2)") (class "Default")
      (node (ref "C53") (pin "2") (pinfunction "2_2") (pintype "passive"))
      (node (ref "C54") (pin "1") (pinfunction "1_1") (pintype "passive"))
      (node (ref "C7") (pin "2") (pinfunction "2_2") (pintype "passive"))
      (node (ref "L10") (pin "2") (pinfunction "2_2") (pintype "passive"))
    )
    (net (code "39") (name "Net-(C54-Pad2)") (class "Default")
      (node (ref "C54") (pin "2") (pinfunction "2_2") (pintype "passive"))
      (node (ref "L11") (pin "1") (pinfunction "1_1") (pintype "passive"))
    )
    (net (code "40") (name "Net-(C56-Pad2)") (class "Default")
      (node (ref "C56") (pin "2") (pinfunction "2_2") (pintype "passive"))
      (node (ref "C57") (pin "2") (pinfunction "2_2") (pintype "passive"))
      (node (ref "L16") (pin "1") (pinfunction "1_1") (pintype "passive"))
      (node (ref "L8") (pin "2") (pinfunction "2_2") (pintype "passive"))
    )
    (net (code "41") (name "Net-(C59-Pad1)") (class "Default")
      (node (ref "C59") (pin "1") (pinfunction "1_1") (pintype "passive"))
      (node (ref "C91") (pin "2") (pinfunction "2_2") (pintype "passive"))
    )
    (net (code "42") (name "Net-(C61-Pad1)") (class "Default")
      (node (ref "C61") (pin "1") (pinfunction "1_1") (pintype "passive"))
      (node (ref "C91") (pin "1") (pinfunction "1_1") (pintype "passive"))
      (node (ref "L17") (pin "2") (pinfunction "2_2") (pintype "passive"))
      (node (ref "L24") (pin "1") (pinfunction "1_1") (pintype "passive"))
    )
    (net (code "43") (name "Net-(C64-Pad1)") (class "Default")
      (node (ref "C64") (pin "1") (pinfunction "1_1") (pintype "passive"))
      (node (ref "C82") (pin "1") (pinfunction "1_1") (pintype "passive"))
      (node (ref "L24") (pin "2") (pinfunction "2_2") (pintype "passive"))
    )
    (net (code "44") (name "Net-(C66-Pad2)") (class "Default")
      (node (ref "C66") (pin "2") (pinfunction "2_2") (pintype "passive"))
      (node (ref "R37") (pin "1") (pinfunction "1_1") (pintype "passive"))
    )
    (net (code "45") (name "Net-(C68-Pad1)") (class "Default")
      (node (ref "C68") (pin "1") (pinfunction "1_1") (pintype "passive"))
      (node (ref "C74") (pin "1") (pinfunction "1_1") (pintype "passive"))
      (node (ref "C75") (pin "2") (pinfunction "2_2") (pintype "passive"))
    )
    (net (code "46") (name "Net-(C77-Pad1)") (class "Default")
      (node (ref "C77") (pin "1") (pinfunction "1_1") (pintype "passive"))
      (node (ref "L21") (pin "1") (pinfunction "1_1") (pintype "passive"))
      (node (ref "R62") (pin "2") (pinfunction "2_2") (pintype "passive"))
    )
    (net (code "47") (name "Net-(C78-Pad1)") (class "Default")
      (node (ref "C78") (pin "1") (pinfunction "1_1") (pintype "passive"))
      (node (ref "C79") (pin "1") (pinfunction "1_1") (pintype "passive"))
      (node (ref "L21") (pin "2") (pinfunction "2_2") (pintype "passive"))
    )
    (net (code "48") (name "Net-(D1-Pad+)") (class "Default")
      (node (ref "D1") (pin "+") (pinfunction "+_+") (pintype "passive"))
      (node (ref "R30") (pin "2") (pinfunction "2_2") (pintype "passive"))
    )
    (net (code "49") (name "Net-(D2-Pad+)") (class "Default")
      (node (ref "D2") (pin "+") (pinfunction "+_+") (pintype "passive"))
      (node (ref "R31") (pin "2") (pinfunction "2_2") (pintype "passive"))
    )
    (net (code "50") (name "Net-(D3-Pad+)") (class "Default")
      (node (ref "D3") (pin "+") (pinfunction "+_+") (pintype "passive"))
      (node (ref "R32") (pin "2") (pinfunction "2_2") (pintype "passive"))
    )
    (net (code "51") (name "Net-(D4-Pad+)") (class "Default")
      (node (ref "D4") (pin "+") (pinfunction "+_+") (pintype "passive"))
      (node (ref "R47") (pin "2") (pinfunction "2_2") (pintype "passive"))
    )
    (net (code "52") (name "Net-(J1-Pad14)") (class "Default")
      (node (ref "J1") (pin "14") (pinfunction "14_14") (pintype "bidirectional"))
      (node (ref "R76") (pin "2") (pinfunction "2_2") (pintype "passive"))
    )
    (net (code "53") (name "Net-(J1-Pad16)") (class "Default")
      (node (ref "J1") (pin "16") (pinfunction "16_16") (pintype "bidirectional"))
      (node (ref "R70") (pin "2") (pinfunction "2_2") (pintype "passive"))
    )
    (net (code "54") (name "Net-(J1-Pad30)") (class "Default")
      (node (ref "J1") (pin "30") (pinfunction "30_30") (pintype "bidirectional"))
      (node (ref "R81") (pin "2") (pinfunction "2_2") (pintype "passive"))
    )
    (net (code "55") (name "Net-(J1-Pad32)") (class "Default")
      (node (ref "J1") (pin "32") (pinfunction "32_32") (pintype "bidirectional"))
      (node (ref "R75") (pin "2") (pinfunction "2_2") (pintype "passive"))
    )
    (net (code "56") (name "Net-(J1-Pad47)") (class "Default")
      (node (ref "J1") (pin "47") (pinfunction "47_47") (pintype "bidirectional"))
      (node (ref "R39") (pin "2") (pinfunction "2_2") (pintype "passive"))
    )
    (net (code "57") (name "Net-(Q10-D)") (class "Default")
      (node (ref "Q10") (pin "3") (pinfunction "D_3") (pintype "passive"))
      (node (ref "Q8") (pin "1") (pinfunction "G_1") (pintype "passive"))
      (node (ref "R78") (pin "2") (pinfunction "2_2") (pintype "passive"))
    )
    (net (code "58") (name "Net-(Q10-G)") (class "Default")
      (node (ref "C92") (pin "2") (pinfunction "2_2") (pintype "passive"))
      (node (ref "Q10") (pin "1") (pinfunction "G_1") (pintype "passive"))
      (node (ref "R79") (pin "2") (pinfunction "2_2") (pintype "passive"))
    )
    (net (code "59") (name "Net-(U1-HOST_MOSI)") (class "Default")
      (node (ref "R5") (pin "1") (pinfunction "1_1") (pintype "passive"))
      (node (ref "U1") (pin "3") (pinfunction "HOST_MOSI_3") (pintype "bidirectional"))
    )
    (net (code "60") (name "Net-(U1-HOST_SCK)") (class "Default")
      (node (ref "R10") (pin "1") (pinfunction "1_1") (pintype "passive"))
      (node (ref "U1") (pin "4") (pinfunction "HOST_SCK_4") (pintype "bidirectional"))
    )
    (net (code "61") (name "Net-(U1-RADIO_A_CLK_I)") (class "Default")
      (node (ref "R25") (pin "1") (pinfunction "1_1") (pintype "passive"))
      (node (ref "U1") (pin "43") (pinfunction "RADIO_A_CLK_I_43") (pintype "bidirectional"))
    )
    (net (code "62") (name "Net-(U1-RADIO_A_IQ0)") (class "Default")
      (node (ref "R26") (pin "1") (pinfunction "1_1") (pintype "passive"))
      (node (ref "U1") (pin "44") (pinfunction "RADIO_A_IQ0_44") (pintype "bidirectional"))
    )
    (net (code "63") (name "Net-(U1-RADIO_A_IQ1)") (class "Default")
      (node (ref "R27") (pin "1") (pinfunction "1_1") (pintype "passive"))
      (node (ref "U1") (pin "45") (pinfunction "RADIO_A_IQ1_45") (pintype "bidirectional"))
    )
    (net (code "64") (name "Net-(U1-RADIO_A_IQ2)") (class "Default")
      (node (ref "R29") (pin "1") (pinfunction "1_1") (pintype "passive"))
      (node (ref "U1") (pin "49") (pinfunction "RADIO_A_IQ2_49") (pintype "bidirectional"))
    )
    (net (code "65") (name "Net-(U1-RADIO_A_IQ3)") (class "Default")
      (node (ref "R24") (pin "1") (pinfunction "1_1") (pintype "passive"))
      (node (ref "U1") (pin "41") (pinfunction "RADIO_A_IQ3_41") (pintype "bidirectional"))
    )
    (net (code "66") (name "Net-(U1-RADIO_A_IQ4)") (class "Default")
      (node (ref "R28") (pin "1") (pinfunction "1_1") (pintype "passive"))
      (node (ref "U1") (pin "48") (pinfunction "RADIO_A_IQ4_48") (pintype "bidirectional"))
    )
    (net (code "67") (name "Net-(U1-RADIO_B_CLK_I)") (class "Default")
      (node (ref "R19") (pin "1") (pinfunction "1_1") (pintype "passive"))
      (node (ref "U1") (pin "34") (pinfunction "RADIO_B_CLK_I_34") (pintype "bidirectional"))
    )
    (net (code "68") (name "Net-(U1-RADIO_B_IQ0)") (class "Default")
      (node (ref "R20") (pin "1") (pinfunction "1_1") (pintype "passive"))
      (node (ref "U1") (pin "35") (pinfunction "RADIO_B_IQ0_35") (pintype "bidirectional"))
    )
    (net (code "69") (name "Net-(U1-RADIO_B_IQ1)") (class "Default")
      (node (ref "R21") (pin "1") (pinfunction "1_1") (pintype "passive"))
      (node (ref "U1") (pin "36") (pinfunction "RADIO_B_IQ1_36") (pintype "bidirectional"))
    )
    (net (code "70") (name "Net-(U1-RADIO_B_IQ2)") (class "Default")
      (node (ref "R23") (pin "1") (pinfunction "1_1") (pintype "passive"))
      (node (ref "U1") (pin "38") (pinfunction "RADIO_B_IQ2_38") (pintype "bidirectional"))
    )
    (net (code "71") (name "Net-(U1-RADIO_B_IQ3)") (class "Default")
      (node (ref "R18") (pin "1") (pinfunction "1_1") (pintype "passive"))
      (node (ref "U1") (pin "32") (pinfunction "RADIO_B_IQ3_32") (pintype "bidirectional"))
    )
    (net (code "72") (name "Net-(U1-RADIO_B_IQ4)") (class "Default")
      (node (ref "R22") (pin "1") (pinfunction "1_1") (pintype "passive"))
      (node (ref "U1") (pin "37") (pinfunction "RADIO_B_IQ4_37") (pintype "bidirectional"))
    )
    (net (code "73") (name "Net-(U1-SP_VALID)") (class "Default")
      (node (ref "R17") (pin "1") (pinfunction "1_1") (pintype "passive"))
      (node (ref "U1") (pin "20") (pinfunction "SP_VALID_20") (pintype "bidirectional"))
    )
    (net (code "74") (name "Net-(U2-IN)") (class "Default")
      (node (ref "C11") (pin "1") (pinfunction "1_1") (pintype "passive"))
      (node (ref "R13") (pin "2") (pinfunction "2_2") (pintype "passive"))
      (node (ref "U2") (pin "2") (pinfunction "IN_2") (pintype "bidirectional"))
    )
    (net (code "75") (name "Net-(U2-OUT)") (class "Default")
      (node (ref "C10") (pin "1") (pinfunction "1_1") (pintype "passive"))
      (node (ref "C6") (pin "1") (pinfunction "1_1") (pintype "passive"))
      (node (ref "C75") (pin "1") (pinfunction "1_1") (pintype "passive"))
      (node (ref "R13") (pin "1") (pinfunction "1_1") (pintype "passive"))
      (node (ref "U2") (pin "5") (pinfunction "OUT_5") (pintype "bidirectional"))
    )
    (net (code "76") (name "Net-(U4-CE)") (class "Default")
      (node (ref "R8") (pin "1") (pinfunction "1_1") (pintype "passive"))
      (node (ref "U4") (pin "3") (pinfunction "CE_3") (pintype "bidirectional"))
    )
    (net (code "77") (name "Net-(U5-DCC_SW)") (class "Default")
      (node (ref "L6") (pin "2") (pinfunction "2_2") (pintype "passive"))
      (node (ref "U5") (pin "8") (pinfunction "DCC_SW_8") (pintype "bidirectional"))
    )
    (net (code "78") (name "Net-(U5-VREG)") (class "Default")
      (node (ref "C34") (pin "2") (pinfunction "2_2") (pintype "passive"))
      (node (ref "L6") (pin "1") (pinfunction "1_1") (pintype "passive"))
      (node (ref "L7") (pin "2") (pinfunction "2_2") (pintype "passive"))
      (node (ref "U5") (pin "6") (pinfunction "VREG_6") (pintype "bidirectional"))
    )
    (net (code "79") (name "Net-(U5-VR_PA)") (class "Default")
      (node (ref "C36") (pin "2") (pinfunction "2_2") (pintype "passive"))
      (node (ref "C37") (pin "2") (pinfunction "2_2") (pintype "passive"))
      (node (ref "L9") (pin "2") (pinfunction "2_2") (pintype "passive"))
      (node (ref "U5") (pin "1") (pinfunction "VR_PA_1") (pintype "bidirectional"))
    )
    (net (code "80") (name "Net-(U5-XTA)") (class "Default")
      (node (ref "C14") (pin "1") (pinfunction "1_1") (pintype "passive"))
      (node (ref "U5") (pin "3") (pinfunction "XTA_3") (pintype "bidirectional"))
    )
    (net (code "81") (name "Net-(U6-EN)") (class "Default")
      (node (ref "R82") (pin "2") (pinfunction "2_2") (pintype "passive"))
      (node (ref "U6") (pin "8") (pinfunction "EN_8") (pintype "bidirectional"))
    )
    (net (code "82") (name "Net-(U6-FB)") (class "Default")
      (node (ref "R83") (pin "1") (pinfunction "1_1") (pintype "passive"))
      (node (ref "R87") (pin "2") (pinfunction "2_2") (pintype "passive"))
      (node (ref "U6") (pin "7") (pinfunction "FB_7") (pintype "bidirectional"))
    )
    (net (code "83") (name "Net-(U6-PG)") (class "Default")
      (node (ref "TP15") (pin "T") (pinfunction "T_T") (pintype "bidirectional"))
      (node (ref "U6") (pin "1") (pinfunction "PG_1") (pintype "bidirectional"))
    )
    (net (code "84") (name "Net-(U6-SW)") (class "Default")
      (node (ref "L5") (pin "1") (pinfunction "1_1") (pintype "passive"))
      (node (ref "U6") (pin "3") (pinfunction "SW_3") (pintype "bidirectional"))
    )
    (net (code "85") (name "Net-(U7-DCC_SW)") (class "Default")
      (node (ref "L14") (pin "2") (pinfunction "2_2") (pintype "passive"))
      (node (ref "U7") (pin "8") (pinfunction "DCC_SW_8") (pintype "bidirectional"))
    )
    (net (code "86") (name "Net-(U7-VREG)") (class "Default")
      (node (ref "C46") (pin "2") (pinfunction "2_2") (pintype "passive"))
      (node (ref "L14") (pin "1") (pinfunction "1_1") (pintype "passive"))
      (node (ref "L15") (pin "2") (pinfunction "2_2") (pintype "passive"))
      (node (ref "U7") (pin "6") (pinfunction "VREG_6") (pintype "bidirectional"))
    )
    (net (code "87") (name "Net-(U7-XTA)") (class "Default")
      (node (ref "C38") (pin "1") (pinfunction "1_1") (pintype "passive"))
      (node (ref "U7") (pin "3") (pinfunction "XTA_3") (pintype "bidirectional"))
    )
    (net (code "88") (name "Net-(U8-IN)") (class "Default")
      (node (ref "C2") (pin "2") (pinfunction "2_2") (pintype "passive"))
      (node (ref "L11") (pin "2") (pinfunction "2_2") (pintype "passive"))
      (node (ref "R52") (pin "1") (pinfunction "1_1") (pintype "passive"))
      (node (ref "U8") (pin "2") (pinfunction "IN_2") (pintype "bidirectional"))
    )
    (net (code "89") (name "Net-(U8-OUT)") (class "Default")
      (node (ref "C8") (pin "1") (pinfunction "1_1") (pintype "passive"))
      (node (ref "R11") (pin "2") (pinfunction "2_2") (pintype "passive"))
      (node (ref "R52") (pin "2") (pinfunction "2_2") (pintype "passive"))
      (node (ref "U8") (pin "5") (pinfunction "OUT_5") (pintype "bidirectional"))
    )
    (net (code "90") (name "Net-(U9-ANT)") (class "Default")
      (node (ref "C59") (pin "2") (pinfunction "2_2") (pintype "passive"))
      (node (ref "C60") (pin "1") (pinfunction "1_1") (pintype "passive"))
      (node (ref "L17") (pin "1") (pinfunction "1_1") (pintype "passive"))
      (node (ref "U9") (pin "9") (pinfunction "ANT_9") (pintype "bidirectional"))
    )
    (net (code "91") (name "Net-(U9-CPS)") (class "Default")
      (node (ref "C17") (pin "2") (pinfunction "2_2") (pintype "passive"))
      (node (ref "R15") (pin "1") (pinfunction "1_1") (pintype "passive"))
      (node (ref "U9") (pin "5") (pinfunction "CPS_5") (pintype "bidirectional"))
    )
    (net (code "92") (name "Net-(U9-CSD)") (class "Default")
      (node (ref "C16") (pin "2") (pinfunction "2_2") (pintype "passive"))
      (node (ref "R14") (pin "1") (pinfunction "1_1") (pintype "passive"))
      (node (ref "U9") (pin "4") (pinfunction "CSD_4") (pintype "bidirectional"))
    )
    (net (code "93") (name "Net-(U9-CTX)") (class "Default")
      (node (ref "C18") (pin "2") (pinfunction "2_2") (pintype "passive"))
      (node (ref "R16") (pin "1") (pinfunction "1_1") (pintype "passive"))
      (node (ref "U9") (pin "6") (pinfunction "CTX_6") (pintype "bidirectional"))
    )
    (net (code "94") (name "Net-(U9-PA_OUT)") (class "Default")
      (node (ref "L2") (pin "1") (pinfunction "1_1") (pintype "passive"))
      (node (ref "L8") (pin "1") (pinfunction "1_1") (pintype "passive"))
      (node (ref "U9") (pin "13") (pinfunction "PA_OUT_13") (pintype "bidirectional"))
    )
    (net (code "95") (name "Net-(U9-RX)") (class "Default")
      (node (ref "C11") (pin "2") (pinfunction "2_2") (pintype "passive"))
      (node (ref "U9") (pin "2") (pinfunction "RX_2") (pintype "bidirectional"))
    )
    (net (code "96") (name "Net-(U9-RX_FLT)") (class "Default")
      (node (ref "R69") (pin "1") (pinfunction "1_1") (pintype "passive"))
      (node (ref "U9") (pin "8") (pinfunction "RX_FLT_8") (pintype "bidirectional"))
    )
    (net (code "97") (name "Net-(U9-TX)") (class "Default")
      (node (ref "C4") (pin "2") (pinfunction "2_2") (pintype "passive"))
      (node (ref "U9") (pin "1") (pinfunction "TX_1") (pintype "bidirectional"))
    )
    (net (code "98") (name "Net-(U9-TX_IN)") (class "Default")
      (node (ref "C58") (pin "2") (pinfunction "2_2") (pintype "passive"))
      (node (ref "L16") (pin "2") (pinfunction "2_2") (pintype "passive"))
      (node (ref "U9") (pin "11") (pinfunction "TX_IN_11") (pintype "bidirectional"))
    )
    (net (code "99") (name "Net-(U9-VCC0)") (class "Default")
      (node (ref "C52") (pin "2") (pinfunction "2_2") (pintype "passive"))
      (node (ref "FB1") (pin "1") (pinfunction "1_1") (pintype "bidirectional"))
      (node (ref "L1") (pin "2") (pinfunction "2_2") (pintype "passive"))
      (node (ref "U9") (pin "15") (pinfunction "VCC0_15") (pintype "bidirectional"))
    )
    (net (code "100") (name "Net-(U9-VCC1)") (class "Default")
      (node (ref "L1") (pin "1") (pinfunction "1_1") (pintype "passive"))
      (node (ref "U9") (pin "16") (pinfunction "VCC1_16") (pintype "bidirectional"))
    )
    (net (code "101") (name "Net-(U10-IN)") (class "Default")
      (node (ref "R35") (pin "2") (pinfunction "2_2") (pintype "passive"))
      (node (ref "R62") (pin "1") (pinfunction "1_1") (pintype "passive"))
      (node (ref "R69") (pin "2") (pinfunction "2_2") (pintype "passive"))
      (node (ref "U10") (pin "2") (pinfunction "IN_2") (pintype "bidirectional"))
    )
    (net (code "102") (name "Net-(U10-OUT)") (class "Default")
      (node (ref "R35") (pin "1") (pinfunction "1_1") (pintype "passive"))
      (node (ref "U10") (pin "5") (pinfunction "OUT_5") (pintype "bidirectional"))
      (node (ref "U9") (pin "7") (pinfunction "LNA_IN_7") (pintype "bidirectional"))
    )
    (net (code "103") (name "Net-(U11-DCC_SW)") (class "Default")
      (node (ref "L20") (pin "2") (pinfunction "2_2") (pintype "passive"))
      (node (ref "U11") (pin "9") (pinfunction "DCC_SW_9") (pintype "bidirectional"))
    )
    (net (code "104") (name "Net-(U11-MOSI)") (class "Default")
      (node (ref "R40") (pin "1") (pinfunction "1_1") (pintype "passive"))
      (node (ref "U11") (pin "17") (pinfunction "MOSI_17") (pintype "bidirectional"))
    )
    (net (code "105") (name "Net-(U11-SCK)") (class "Default")
      (node (ref "R41") (pin "1") (pinfunction "1_1") (pintype "passive"))
      (node (ref "U11") (pin "18") (pinfunction "SCK_18") (pintype "bidirectional"))
    )
    (net (code "106") (name "Net-(U11-VDD_IN)") (class "Default")
      (node (ref "C65") (pin "1") (pinfunction "1_1") (pintype "passive"))
      (node (ref "L18") (pin "2") (pinfunction "2_2") (pintype "passive"))
      (node (ref "R36") (pin "2") (pinfunction "2_2") (pintype "passive"))
      (node (ref "U11") (pin "1") (pinfunction "VDD_IN_1") (pintype "bidirectional"))
    )
    (net (code "107") (name "Net-(U11-VREG)") (class "Default")
      (node (ref "C63") (pin "1") (pinfunction "1_1") (pintype "passive"))
      (node (ref "L18") (pin "1") (pinfunction "1_1") (pintype "passive"))
      (node (ref "L20") (pin "1") (pinfunction "1_1") (pintype "passive"))
      (node (ref "U11") (pin "7") (pinfunction "VREG_7") (pintype "bidirectional"))
    )
    (net (code "108") (name "Net-(U11-XTA)") (class "Default")
      (node (ref "C66") (pin "1") (pinfunction "1_1") (pintype "passive"))
      (node (ref "U11") (pin "3") (pinfunction "XTA_3") (pintype "bidirectional"))
    )
    (net (code "109") (name "Net-(U12-BOOT0)") (class "Default")
      (node (ref "R56") (pin "2") (pinfunction "2_2") (pintype "passive"))
      (node (ref "R57") (pin "1") (pinfunction "1_1") (pintype "passive"))
      (node (ref "U12") (pin "31") (pinfunction "BOOT0_31") (pintype "bidirectional"))
    )
    (net (code "110") (name "Net-(U12-PA0-CLK_IN)") (class "Default")
      (node (ref "R72") (pin "2") (pinfunction "2_2") (pintype "passive"))
      (node (ref "R73") (pin "2") (pinfunction "2_2") (pintype "passive"))
      (node (ref "U12") (pin "6") (pinfunction "PA0-CLK_IN_6") (pintype "bidirectional"))
    )
    (net (code "111") (name "Net-(U12-PA11)") (class "Default")
      (node (ref "R66") (pin "2") (pinfunction "2_2") (pintype "passive"))
      (node (ref "U12") (pin "21") (pinfunction "PA11_21") (pintype "bidirectional"))
    )
    (net (code "112") (name "Net-(U12-PA12)") (class "Default")
      (node (ref "R64") (pin "2") (pinfunction "2_2") (pintype "passive"))
      (node (ref "U12") (pin "22") (pinfunction "PA12_22") (pintype "bidirectional"))
    )
    (net (code "113") (name "Net-(U12-PC14-OSC32_IN)") (class "Default")
      (node (ref "C81") (pin "1") (pinfunction "1_1") (pintype "passive"))
      (node (ref "U12") (pin "2") (pinfunction "PC14-OSC32_IN_2") (pintype "bidirectional"))
      (node (ref "X3") (pin "2") (pinfunction "2_2") (pintype "passive"))
    )
    (net (code "114") (name "Net-(U12-PC15-OSC32_OUT)") (class "Default")
      (node (ref "C84") (pin "1") (pinfunction "1_1") (pintype "passive"))
      (node (ref "U12") (pin "3") (pinfunction "PC15-OSC32_OUT_3") (pintype "bidirectional"))
      (node (ref "X3") (pin "1") (pinfunction "1_1") (pintype "passive"))
    )
    (net (code "115") (name "Net-(U13-~{EVENT})") (class "Default")
      (node (ref "R65") (pin "2") (pinfunction "2_2") (pintype "passive"))
      (node (ref "U13") (pin "2") (pinfunction "~{EVENT}_2") (pintype "bidirectional"))
    )
    (net (code "116") (name "Net-(X1-ENABLE)") (class "Default")
      (node (ref "R3") (pin "1") (pinfunction "1_1") (pintype "passive"))
      (node (ref "R4") (pin "2") (pinfunction "2_2") (pintype "passive"))
      (node (ref "X1") (pin "1") (pinfunction "ENABLE_1") (pintype "bidirectional"))
    )
    (net (code "117") (name "Net-(X1-VDD)") (class "Default")
      (node (ref "C62") (pin "2") (pinfunction "2_2") (pintype "passive"))
      (node (ref "L4") (pin "1") (pinfunction "1_1") (pintype "bidirectional"))
      (node (ref "R3") (pin "2") (pinfunction "2_2") (pintype "passive"))
      (node (ref "X1") (pin "4") (pinfunction "VDD_4") (pintype "bidirectional"))
    )
    (net (code "118") (name "PPS") (class "Default")
      (node (ref "J1") (pin "19") (pinfunction "19_19") (pintype "bidirectional"))
      (node (ref "TP2") (pin "T") (pinfunction "T_T") (pintype "bidirectional"))
      (node (ref "U1") (pin "8") (pinfunction "PPS_8") (pintype "bidirectional"))
      (node (ref "U12") (pin "27") (pinfunction "PB4_27") (pintype "bidirectional"))
    )
    (net (code "119") (name "RADIO_A_CLK_32M") (class "Default")
      (node (ref "R25") (pin "2") (pinfunction "2_2") (pintype "passive"))
      (node (ref "R72") (pin "1") (pinfunction "1_1") (pintype "passive"))
      (node (ref "U5") (pin "14") (pinfunction "BUSY_14") (pintype "bidirectional"))
    )
    (net (code "120") (name "RADIO_A_CLK_O") (class "Default")
      (node (ref "R28") (pin "2") (pinfunction "2_2") (pintype "passive"))
      (node (ref "U5") (pin "11") (pinfunction "DIO5_11") (pintype "bidirectional"))
    )
    (net (code "121") (name "RADIO_A_CSN") (class "Default")
      (node (ref "U1") (pin "68") (pinfunction "RADIO_A_CSN_68") (pintype "bidirectional"))
      (node (ref "U5") (pin "19") (pinfunction "NSS_19") (pintype "bidirectional"))
    )
    (net (code "122") (name "RADIO_A_IQ_0") (class "Default")
      (node (ref "R26") (pin "2") (pinfunction "2_2") (pintype "passive"))
      (node (ref "U5") (pin "13") (pinfunction "DIO1_13") (pintype "bidirectional"))
    )
    (net (code "123") (name "RADIO_A_IQ_1") (class "Default")
      (node (ref "R27") (pin "2") (pinfunction "2_2") (pintype "passive"))
      (node (ref "U5") (pin "12") (pinfunction "DIO2_12") (pintype "bidirectional"))
    )
    (net (code "124") (name "RADIO_A_IQ_2") (class "Default")
      (node (ref "R29") (pin "2") (pinfunction "2_2") (pintype "passive"))
      (node (ref "U5") (pin "5") (pinfunction "DIO3_5") (pintype "bidirectional"))
    )
    (net (code "125") (name "RADIO_A_IQ_3") (class "Default")
      (node (ref "R24") (pin "2") (pinfunction "2_2") (pintype "passive"))
      (node (ref "U5") (pin "21") (pinfunction "DIO4_21") (pintype "bidirectional"))
    )
    (net (code "126") (name "RADIO_A_RESET") (class "Default")
      (node (ref "U1") (pin "13") (pinfunction "RADIO_CTRL3_13") (pintype "bidirectional"))
      (node (ref "U5") (pin "15") (pinfunction "NRESET_15") (pintype "bidirectional"))
    )
    (net (code "127") (name "RADIO_A_RFIN") (class "Default")
      (node (ref "C6") (pin "2") (pinfunction "2_2") (pintype "passive"))
      (node (ref "L12") (pin "2") (pinfunction "2_2") (pintype "passive"))
      (node (ref "U5") (pin "23") (pinfunction "RFI_N_23") (pintype "bidirectional"))
    )
    (net (code "128") (name "RADIO_A_RFIP") (class "Default")
      (node (ref "C5") (pin "2") (pinfunction "2_2") (pintype "passive"))
      (node (ref "L12") (pin "1") (pinfunction "1_1") (pintype "passive"))
      (node (ref "U5") (pin "22") (pinfunction "RFI_P_22") (pintype "bidirectional"))
    )
    (net (code "129") (name "RADIO_B_CLK_32M") (class "Default")
      (node (ref "R19") (pin "2") (pinfunction "2_2") (pintype "passive"))
      (node (ref "U7") (pin "14") (pinfunction "BUSY_14") (pintype "bidirectional"))
    )
    (net (code "130") (name "RADIO_B_CLK_O") (class "Default")
      (node (ref "R22") (pin "2") (pinfunction "2_2") (pintype "passive"))
      (node (ref "U7") (pin "11") (pinfunction "DIO5_11") (pintype "bidirectional"))
    )
    (net (code "131") (name "RADIO_B_CSN") (class "Default")
      (node (ref "U1") (pin "18") (pinfunction "RADIO_B_CSN_18") (pintype "bidirectional"))
      (node (ref "U7") (pin "19") (pinfunction "NSS_19") (pintype "bidirectional"))
    )
    (net (code "132") (name "RADIO_B_IQ0") (class "Default")
      (node (ref "R20") (pin "2") (pinfunction "2_2") (pintype "passive"))
      (node (ref "U7") (pin "13") (pinfunction "DIO1_13") (pintype "bidirectional"))
    )
    (net (code "133") (name "RADIO_B_IQ_1") (class "Default")
      (node (ref "R21") (pin "2") (pinfunction "2_2") (pintype "passive"))
      (node (ref "U7") (pin "12") (pinfunction "DIO2_12") (pintype "bidirectional"))
    )
    (net (code "134") (name "RADIO_B_IQ_2") (class "Default")
      (node (ref "R23") (pin "2") (pinfunction "2_2") (pintype "passive"))
      (node (ref "U7") (pin "5") (pinfunction "DIO3_5") (pintype "bidirectional"))
    )
    (net (code "135") (name "RADIO_B_IQ_3") (class "Default")
      (node (ref "R18") (pin "2") (pinfunction "2_2") (pintype "passive"))
      (node (ref "U7") (pin "21") (pinfunction "DIO4_21") (pintype "bidirectional"))
    )
    (net (code "136") (name "RADIO_B_RESET") (class "Default")
      (node (ref "U1") (pin "28") (pinfunction "RADIO_CTRL9_28") (pintype "bidirectional"))
      (node (ref "U7") (pin "15") (pinfunction "NRESET_15") (pintype "bidirectional"))
    )
    (net (code "137") (name "RADIO_B_RFIN") (class "Default")
      (node (ref "C10") (pin "2") (pinfunction "2_2") (pintype "passive"))
      (node (ref "L13") (pin "2") (pinfunction "2_2") (pintype "passive"))
      (node (ref "U7") (pin "23") (pinfunction "RFI_N_23") (pintype "bidirectional"))
    )
    (net (code "138") (name "RADIO_B_RFIP") (class "Default")
      (node (ref "C9") (pin "2") (pinfunction "2_2") (pintype "passive"))
      (node (ref "L13") (pin "1") (pinfunction "1_1") (pintype "passive"))
      (node (ref "U7") (pin "22") (pinfunction "RFI_P_22") (pintype "bidirectional"))
    )
    (net (code "139") (name "RFO") (class "Default")
      (node (ref "C53") (pin "1") (pinfunction "1_1") (pintype "passive"))
      (node (ref "L10") (pin "1") (pinfunction "1_1") (pintype "passive"))
      (node (ref "L9") (pin "1") (pinfunction "1_1") (pintype "passive"))
      (node (ref "U5") (pin "24") (pinfunction "RFO_24") (pintype "bidirectional"))
    )
    (net (code "140") (name "RX_ON") (class "Default")
      (node (ref "R32") (pin "1") (pinfunction "1_1") (pintype "passive"))
      (node (ref "U1") (pin "59") (pinfunction "GPIO4_59") (pintype "bidirectional"))
    )
    (net (code "141") (name "SCK") (class "Default")
      (node (ref "R10") (pin "2") (pinfunction "2_2") (pintype "passive"))
      (node (ref "R41") (pin "2") (pinfunction "2_2") (pintype "passive"))
      (node (ref "R49") (pin "1") (pinfunction "1_1") (pintype "passive"))
      (node (ref "R50") (pin "1") (pinfunction "1_1") (pintype "passive"))
    )
    (net (code "142") (name "SCK_A") (class "Default")
      (node (ref "U1") (pin "65") (pinfunction "RADIO_A_SCK_65") (pintype "bidirectional"))
      (node (ref "U5") (pin "18") (pinfunction "SCK_18") (pintype "bidirectional"))
    )
    (net (code "143") (name "SCK_B") (class "Default")
      (node (ref "U1") (pin "21") (pinfunction "RADIO_B_SCK_21") (pintype "bidirectional"))
      (node (ref "U7") (pin "18") (pinfunction "SCK_18") (pintype "bidirectional"))
    )
    (net (code "144") (name "STM32_MISO") (class "Default")
      (node (ref "R45") (pin "2") (pinfunction "2_2") (pintype "passive"))
      (node (ref "U12") (pin "12") (pinfunction "PA6_12") (pintype "bidirectional"))
    )
    (net (code "145") (name "STM32_MOSI") (class "Default")
      (node (ref "R48") (pin "2") (pinfunction "2_2") (pintype "passive"))
      (node (ref "U12") (pin "13") (pinfunction "PA7_13") (pintype "bidirectional"))
    )
    (net (code "146") (name "STM32_SCK") (class "Default")
      (node (ref "R50") (pin "2") (pinfunction "2_2") (pintype "passive"))
      (node (ref "U12") (pin "11") (pinfunction "PA5_11") (pintype "bidirectional"))
    )
    (net (code "147") (name "SWCLK") (class "Default")
      (node (ref "TP7") (pin "T") (pinfunction "T_T") (pintype "bidirectional"))
      (node (ref "U12") (pin "24") (pinfunction "PA14_24") (pintype "bidirectional"))
    )
    (net (code "148") (name "SWDIO") (class "Default")
      (node (ref "TP8") (pin "T") (pinfunction "T_T") (pintype "bidirectional"))
      (node (ref "U12") (pin "23") (pinfunction "PA13_23") (pintype "bidirectional"))
    )
    (net (code "149") (name "SX1261_BUSY") (class "Default")
      (node (ref "R67") (pin "1") (pinfunction "1_1") (pintype "passive"))
      (node (ref "U11") (pin "14") (pinfunction "BUSY_14") (pintype "bidirectional"))
      (node (ref "U12") (pin "9") (pinfunction "PA3_9") (pintype "bidirectional"))
    )
    (net (code "150") (name "SX1261_CS") (class "Default")
      (node (ref "R42") (pin "1") (pinfunction "1_1") (pintype "passive"))
      (node (ref "R51") (pin "1") (pinfunction "1_1") (pintype "passive"))
      (node (ref "U11") (pin "19") (pinfunction "NSS_19") (pintype "bidirectional"))
      (node (ref "U12") (pin "14") (pinfunction "PB0_14") (pintype "bidirectional"))
    )
    (net (code "151") (name "SX1261_IO1") (class "Default")
      (node (ref "R61") (pin "1") (pinfunction "1_1") (pintype "passive"))
      (node (ref "U1") (pin "54") (pinfunction "GPIO7_54") (pintype "bidirectional"))
      (node (ref "U11") (pin "13") (pinfunction "DIO1_13") (pintype "bidirectional"))
      (node (ref "U12") (pin "15") (pinfunction "PB1_15") (pintype "bidirectional"))
    )
    (net (code "152") (name "SX1261_IO2") (class "Default")
      (node (ref "R63") (pin "1") (pinfunction "1_1") (pintype "passive"))
      (node (ref "U11") (pin "12") (pinfunction "DIO2_12") (pintype "bidirectional"))
    )
    (net (code "153") (name "SX1261_IO3") (class "Default")
      (node (ref "TP9") (pin "T") (pinfunction "T_T") (pintype "bidirectional"))
      (node (ref "U11") (pin "6") (pinfunction "DIO3_6") (pintype "bidirectional"))
    )
    (net (code "154") (name "SX1261_RFIN") (class "Default")
      (node (ref "C68") (pin "2") (pinfunction "2_2") (pintype "passive"))
      (node (ref "L22") (pin "2") (pinfunction "2_2") (pintype "passive"))
      (node (ref "U11") (pin "22") (pinfunction "RFI_N_22") (pintype "bidirectional"))
    )
    (net (code "155") (name "SX1261_RFIP") (class "Default")
      (node (ref "C73") (pin "1") (pinfunction "1_1") (pintype "passive"))
      (node (ref "L22") (pin "1") (pinfunction "1_1") (pintype "passive"))
      (node (ref "U11") (pin "21") (pinfunction "RFI_P_21") (pintype "bidirectional"))
    )
    (net (code "156") (name "SX1261_RST") (class "Default")
      (node (ref "R38") (pin "1") (pinfunction "1_1") (pintype "passive"))
      (node (ref "R60") (pin "1") (pinfunction "1_1") (pintype "passive"))
      (node (ref "U11") (pin "15") (pinfunction "NRESET_15") (pintype "bidirectional"))
      (node (ref "U12") (pin "18") (pinfunction "PA8_18") (pintype "bidirectional"))
    )
    (net (code "157") (name "SX1302_GPIO8") (class "Default")
      (node (ref "U1") (pin "53") (pinfunction "GPIO8_53") (pintype "bidirectional"))
      (node (ref "U12") (pin "26") (pinfunction "PB3_26") (pintype "bidirectional"))
    )
    (net (code "158") (name "TX_ON") (class "Default")
      (node (ref "R30") (pin "1") (pinfunction "1_1") (pintype "passive"))
      (node (ref "U1") (pin "63") (pinfunction "GPIO2_63") (pintype "bidirectional"))
    )
    (net (code "159") (name "TX_RX_SW") (class "Default")
      (node (ref "R16") (pin "2") (pinfunction "2_2") (pintype "passive"))
      (node (ref "U1") (pin "12") (pinfunction "RADIO_CTRL2_12") (pintype "bidirectional"))
    )
    (net (code "160") (name "VCCIO") (class "Default")
      (node (ref "C19") (pin "2") (pinfunction "2_2") (pintype "passive"))
      (node (ref "C20") (pin "2") (pinfunction "2_2") (pintype "passive"))
      (node (ref "C25") (pin "2") (pinfunction "2_2") (pintype "passive"))
      (node (ref "C28") (pin "2") (pinfunction "2_2") (pintype "passive"))
      (node (ref "C3") (pin "2") (pinfunction "2_2") (pintype "passive"))
      (node (ref "C41") (pin "2") (pinfunction "2_2") (pintype "passive"))
      (node (ref "C42") (pin "2") (pinfunction "2_2") (pintype "passive"))
      (node (ref "C45") (pin "2") (pinfunction "2_2") (pintype "passive"))
      (node (ref "C47") (pin "2") (pinfunction "2_2") (pintype "passive"))
      (node (ref "C76") (pin "2") (pinfunction "2_2") (pintype "passive"))
      (node (ref "C80") (pin "2") (pinfunction "2_2") (pintype "passive"))
      (node (ref "C83") (pin "2") (pinfunction "2_2") (pintype "passive"))
      (node (ref "C86") (pin "2") (pinfunction "2_2") (pintype "passive"))
      (node (ref "C87") (pin "2") (pinfunction "2_2") (pintype "passive"))
      (node (ref "C88") (pin "2") (pinfunction "2_2") (pintype "passive"))
      (node (ref "C89") (pin "2") (pinfunction "2_2") (pintype "passive"))
      (node (ref "C90") (pin "2") (pinfunction "2_2") (pintype "passive"))
      (node (ref "Q8") (pin "3") (pinfunction "D_3") (pintype "passive"))
      (node (ref "R33") (pin "1") (pinfunction "1_1") (pintype "passive"))
      (node (ref "R34") (pin "2") (pinfunction "2_2") (pintype "passive"))
      (node (ref "R56") (pin "1") (pinfunction "1_1") (pintype "passive"))
      (node (ref "R58") (pin "1") (pinfunction "1_1") (pintype "passive"))
      (node (ref "R65") (pin "1") (pinfunction "1_1") (pintype "passive"))
      (node (ref "R68") (pin "1") (pinfunction "1_1") (pintype "passive"))
      (node (ref "R71") (pin "1") (pinfunction "1_1") (pintype "passive"))
      (node (ref "R80") (pin "2") (pinfunction "2_2") (pintype "passive"))
      (node (ref "TP1") (pin "T") (pinfunction "T_T") (pintype "bidirectional"))
      (node (ref "U1") (pin "14") (pinfunction "VCC_IO_14") (pintype "bidirectional"))
      (node (ref "U1") (pin "30") (pinfunction "VCC_IO_30") (pintype "bidirectional"))
      (node (ref "U1") (pin "47") (pinfunction "VCC_IO_47") (pintype "bidirectional"))
      (node (ref "U1") (pin "61") (pinfunction "VCC_IO_61") (pintype "bidirectional"))
      (node (ref "U12") (pin "1") (pinfunction "VDD_1") (pintype "bidirectional"))
      (node (ref "U12") (pin "17") (pinfunction "VDD_17") (pintype "bidirectional"))
      (node (ref "U12") (pin "5") (pinfunction "VDDA_5") (pintype "bidirectional"))
      (node (ref "U13") (pin "3") (pinfunction "VDD_3") (pintype "bidirectional"))
    )
    (net (code "161") (name "VCC_1V2") (class "Default")
      (node (ref "C12") (pin "2") (pinfunction "2_2") (pintype "passive"))
      (node (ref "C13") (pin "2") (pinfunction "2_2") (pintype "passive"))
      (node (ref "C23") (pin "2") (pinfunction "2_2") (pintype "passive"))
      (node (ref "C24") (pin "2") (pinfunction "2_2") (pintype "passive"))
      (node (ref "C29") (pin "2") (pinfunction "2_2") (pintype "passive"))
      (node (ref "C40") (pin "2") (pinfunction "2_2") (pintype "passive"))
      (node (ref "C43") (pin "2") (pinfunction "2_2") (pintype "passive"))
      (node (ref "C44") (pin "2") (pinfunction "2_2") (pintype "passive"))
      (node (ref "C71") (pin "2") (pinfunction "2_2") (pintype "passive"))
      (node (ref "C72") (pin "2") (pinfunction "2_2") (pintype "passive"))
      (node (ref "L5") (pin "2") (pinfunction "2_2") (pintype "passive"))
      (node (ref "R79") (pin "1") (pinfunction "1_1") (pintype "passive"))
      (node (ref "R83") (pin "2") (pinfunction "2_2") (pintype "passive"))
      (node (ref "TP14") (pin "T") (pinfunction "T_T") (pintype "bidirectional"))
      (node (ref "U1") (pin "23") (pinfunction "VCC_CORE_23") (pintype "bidirectional"))
      (node (ref "U1") (pin "40") (pinfunction "VCC_CORE_40") (pintype "bidirectional"))
      (node (ref "U1") (pin "5") (pinfunction "VCC_CORE_5") (pintype "bidirectional"))
      (node (ref "U1") (pin "56") (pinfunction "VCC_CORE_56") (pintype "bidirectional"))
      (node (ref "U6") (pin "5") (pinfunction "OUT_5") (pintype "bidirectional"))
    )
    (net (code "162") (name "VCC_FEM") (class "Default")
      (node (ref "C26") (pin "2") (pinfunction "2_2") (pintype "passive"))
      (node (ref "C27") (pin "2") (pinfunction "2_2") (pintype "passive"))
      (node (ref "C49") (pin "2") (pinfunction "2_2") (pintype "passive"))
      (node (ref "C50") (pin "2") (pinfunction "2_2") (pintype "passive"))
      (node (ref "C51") (pin "2") (pinfunction "2_2") (pintype "passive"))
      (node (ref "C55") (pin "2") (pinfunction "2_2") (pintype "passive"))
      (node (ref "FB1") (pin "2") (pinfunction "2_2") (pintype "bidirectional"))
      (node (ref "L2") (pin "2") (pinfunction "2_2") (pintype "passive"))
      (node (ref "R2") (pin "2") (pinfunction "2_2") (pintype "passive"))
      (node (ref "TP6") (pin "T") (pinfunction "T_T") (pintype "bidirectional"))
      (node (ref "U3") (pin "5") (pinfunction "VOUT_5") (pintype "bidirectional"))
    )
    (net (code "163") (name "VCC_RADIO") (class "Default")
      (node (ref "C21") (pin "2") (pinfunction "2_2") (pintype "passive"))
      (node (ref "C32") (pin "2") (pinfunction "2_2") (pintype "passive"))
      (node (ref "C33") (pin "2") (pinfunction "2_2") (pintype "passive"))
      (node (ref "C35") (pin "2") (pinfunction "2_2") (pintype "passive"))
      (node (ref "C39") (pin "2") (pinfunction "2_2") (pintype "passive"))
      (node (ref "C48") (pin "2") (pinfunction "2_2") (pintype "passive"))
      (node (ref "C67") (pin "1") (pinfunction "1_1") (pintype "passive"))
      (node (ref "L15") (pin "1") (pinfunction "1_1") (pintype "passive"))
      (node (ref "L4") (pin "2") (pinfunction "2_2") (pintype "bidirectional"))
      (node (ref "L7") (pin "1") (pinfunction "1_1") (pintype "passive"))
      (node (ref "R36") (pin "1") (pinfunction "1_1") (pintype "passive"))
      (node (ref "R38") (pin "2") (pinfunction "2_2") (pintype "passive"))
      (node (ref "R42") (pin "2") (pinfunction "2_2") (pintype "passive"))
      (node (ref "R7") (pin "2") (pinfunction "2_2") (pintype "passive"))
      (node (ref "TP10") (pin "T") (pinfunction "T_T") (pintype "bidirectional"))
      (node (ref "U11") (pin "10") (pinfunction "VBAT_10") (pintype "bidirectional"))
      (node (ref "U11") (pin "11") (pinfunction "VBAT_IO_11") (pintype "bidirectional"))
      (node (ref "U4") (pin "5") (pinfunction "VOUT_5") (pintype "bidirectional"))
      (node (ref "U5") (pin "10") (pinfunction "VBAT_DIO_10") (pintype "bidirectional"))
      (node (ref "U5") (pin "2") (pinfunction "VDD_IN_2") (pintype "bidirectional"))
      (node (ref "U5") (pin "9") (pinfunction "VBAT_RF_9") (pintype "bidirectional"))
      (node (ref "U7") (pin "10") (pinfunction "VBAT_DIO_10") (pintype "bidirectional"))
      (node (ref "U7") (pin "2") (pinfunction "VDD_IN_2") (pintype "bidirectional"))
      (node (ref "U7") (pin "9") (pinfunction "VBAT_RF_9") (pintype "bidirectional"))
    )
    (net (code "164") (name "VIN") (class "Default")
      (node (ref "C15") (pin "2") (pinfunction "2_2") (pintype "passive"))
      (node (ref "C22") (pin "2") (pinfunction "2_2") (pintype "passive"))
      (node (ref "C30") (pin "2") (pinfunction "2_2") (pintype "passive"))
      (node (ref "C31") (pin "2") (pinfunction "2_2") (pintype "passive"))
      (node (ref "C69") (pin "2") (pinfunction "2_2") (pintype "passive"))
      (node (ref "C70") (pin "2") (pinfunction "2_2") (pintype "passive"))
      (node (ref "J1") (pin "2") (pinfunction "3V3_2") (pintype "bidirectional"))
      (node (ref "J1") (pin "24") (pinfunction "3V3_24") (pintype "bidirectional"))
      (node (ref "J1") (pin "39") (pinfunction "3V3_39") (pintype "bidirectional"))
      (node (ref "J1") (pin "41") (pinfunction "3V3_41") (pintype "bidirectional"))
      (node (ref "J1") (pin "52") (pinfunction "3V3_52") (pintype "bidirectional"))
      (node (ref "Q8") (pin "2") (pinfunction "S_2") (pintype "passive"))
      (node (ref "R2") (pin "1") (pinfunction "1_1") (pintype "passive"))
      (node (ref "R47") (pin "1") (pinfunction "1_1") (pintype "passive"))
      (node (ref "R7") (pin "1") (pinfunction "1_1") (pintype "passive"))
      (node (ref "R78") (pin "1") (pinfunction "1_1") (pintype "passive"))
      (node (ref "R8") (pin "2") (pinfunction "2_2") (pintype "passive"))
      (node (ref "R82") (pin "1") (pinfunction "1_1") (pintype "passive"))
      (node (ref "TP4") (pin "T") (pinfunction "T_T") (pintype "bidirectional"))
      (node (ref "U3") (pin "1") (pinfunction "VIN_1") (pintype "bidirectional"))
      (node (ref "U4") (pin "1") (pinfunction "VIN_1") (pintype "bidirectional"))
      (node (ref "U6") (pin "2") (pinfunction "VIN_2") (pintype "bidirectional"))
    )
    (net (code "165") (name "unconnected-(J1-1V5-Pad6)") (class "Default")
      (node (ref "J1") (pin "6") (pinfunction "1V5_6") (pintype "bidirectional"))
    )
    (net (code "166") (name "unconnected-(J1-1V5-Pad28)") (class "Default")
      (node (ref "J1") (pin "28") (pinfunction "1V5_28") (pintype "bidirectional"))
    )
    (net (code "167") (name "unconnected-(J1-1V5-Pad48)") (class "Default")
      (node (ref "J1") (pin "48") (pinfunction "1V5_48") (pintype "bidirectional"))
    )
    (net (code "168") (name "unconnected-(J1-Pad1)") (class "Default")
      (node (ref "J1") (pin "1") (pinfunction "1_1") (pintype "bidirectional"))
    )
    (net (code "169") (name "unconnected-(J1-Pad3)") (class "Default")
      (node (ref "J1") (pin "3") (pinfunction "3_3") (pintype "bidirectional"))
    )
    (net (code "170") (name "unconnected-(J1-Pad5)") (class "Default")
      (node (ref "J1") (pin "5") (pinfunction "5_5") (pintype "bidirectional"))
    )
    (net (code "171") (name "unconnected-(J1-Pad7)") (class "Default")
      (node (ref "J1") (pin "7") (pinfunction "7_7") (pintype "bidirectional"))
    )
    (net (code "172") (name "unconnected-(J1-Pad11)") (class "Default")
      (node (ref "J1") (pin "11") (pinfunction "11_11") (pintype "bidirectional"))
    )
    (net (code "173") (name "unconnected-(J1-Pad13)") (class "Default")
      (node (ref "J1") (pin "13") (pinfunction "13_13") (pintype "bidirectional"))
    )
    (net (code "174") (name "unconnected-(J1-Pad17)") (class "Default")
      (node (ref "J1") (pin "17") (pinfunction "17_17") (pintype "bidirectional"))
    )
    (net (code "175") (name "unconnected-(J1-Pad20)") (class "Default")
      (node (ref "J1") (pin "20") (pinfunction "20_20") (pintype "bidirectional"))
    )
    (net (code "176") (name "unconnected-(J1-Pad42)") (class "Default")
      (node (ref "J1") (pin "42") (pinfunction "42_42") (pintype "bidirectional"))
    )
    (net (code "177") (name "unconnected-(J1-Pad44)") (class "Default")
      (node (ref "J1") (pin "44") (pinfunction "44_44") (pintype "bidirectional"))
    )
    (net (code "178") (name "unconnected-(J1-Pad46)") (class "Default")
      (node (ref "J1") (pin "46") (pinfunction "46_46") (pintype "bidirectional"))
    )
    (net (code "179") (name "unconnected-(U1-GPIO1-Pad64)") (class "Default")
      (node (ref "U1") (pin "64") (pinfunction "GPIO1_64") (pintype "bidirectional"))
    )
    (net (code "180") (name "unconnected-(U1-GPIO3-Pad60)") (class "Default")
      (node (ref "U1") (pin "60") (pinfunction "GPIO3_60") (pintype "bidirectional"))
    )
    (net (code "181") (name "unconnected-(U1-GPIO5-Pad58)") (class "Default")
      (node (ref "U1") (pin "58") (pinfunction "GPIO5_58") (pintype "bidirectional"))
    )
    (net (code "182") (name "unconnected-(U1-GPIO6-Pad57)") (class "Default")
      (node (ref "U1") (pin "57") (pinfunction "GPIO6_57") (pintype "bidirectional"))
    )
    (net (code "183") (name "unconnected-(U1-GPIO9-Pad52)") (class "Default")
      (node (ref "U1") (pin "52") (pinfunction "GPIO9_52") (pintype "bidirectional"))
    )
    (net (code "184") (name "unconnected-(U1-GPIO10-Pad51)") (class "Default")
      (node (ref "U1") (pin "51") (pinfunction "GPIO10_51") (pintype "bidirectional"))
    )
    (net (code "185") (name "unconnected-(U1-GPIO11-Pad50)") (class "Default")
      (node (ref "U1") (pin "50") (pinfunction "GPIO11_50") (pintype "bidirectional"))
    )
    (net (code "186") (name "unconnected-(U1-RADIO_CTRL1-Pad11)") (class "Default")
      (node (ref "U1") (pin "11") (pinfunction "RADIO_CTRL1_11") (pintype "bidirectional"))
    )
    (net (code "187") (name "unconnected-(U1-RADIO_CTRL5-Pad17)") (class "Default")
      (node (ref "U1") (pin "17") (pinfunction "RADIO_CTRL5_17") (pintype "bidirectional"))
    )
    (net (code "188") (name "unconnected-(U1-RADIO_CTRL6-Pad22)") (class "Default")
      (node (ref "U1") (pin "22") (pinfunction "RADIO_CTRL6_22") (pintype "bidirectional"))
    )
    (net (code "189") (name "unconnected-(U1-RADIO_CTRL7-Pad26)") (class "Default")
      (node (ref "U1") (pin "26") (pinfunction "RADIO_CTRL7_26") (pintype "bidirectional"))
    )
    (net (code "190") (name "unconnected-(U1-RADIO_CTRL8-Pad27)") (class "Default")
      (node (ref "U1") (pin "27") (pinfunction "RADIO_CTRL8_27") (pintype "bidirectional"))
    )
    (net (code "191") (name "unconnected-(U1-RADIO_CTRL10-Pad29)") (class "Default")
      (node (ref "U1") (pin "29") (pinfunction "RADIO_CTRL10_29") (pintype "bidirectional"))
    )
    (net (code "192") (name "unconnected-(U1-RADIO_CTRL11-Pad31)") (class "Default")
      (node (ref "U1") (pin "31") (pinfunction "RADIO_CTRL11_31") (pintype "bidirectional"))
    )
    (net (code "193") (name "unconnected-(U3-NC-Pad4)") (class "Default")
      (node (ref "U3") (pin "4") (pinfunction "NC_4") (pintype "bidirectional"))
    )
    (net (code "194") (name "unconnected-(U4-NC-Pad4)") (class "Default")
      (node (ref "U4") (pin "4") (pinfunction "NC_4") (pintype "bidirectional"))
    )
    (net (code "195") (name "unconnected-(U5-XTB-Pad4)") (class "Default")
      (node (ref "U5") (pin "4") (pinfunction "XTB_4") (pintype "bidirectional"))
    )
    (net (code "196") (name "unconnected-(U7-RFO-Pad24)") (class "Default")
      (node (ref "U7") (pin "24") (pinfunction "RFO_24") (pintype "bidirectional"))
    )
    (net (code "197") (name "unconnected-(U7-VR_PA-Pad1)") (class "Default")
      (node (ref "U7") (pin "1") (pinfunction "VR_PA_1") (pintype "bidirectional"))
    )
    (net (code "198") (name "unconnected-(U7-XTB-Pad4)") (class "Default")
      (node (ref "U7") (pin "4") (pinfunction "XTB_4") (pintype "bidirectional"))
    )
    (net (code "199") (name "unconnected-(U9-NC-Pad14)") (class "Default")
      (node (ref "U9") (pin "14") (pinfunction "NC_14") (pintype "bidirectional"))
    )
    (net (code "200") (name "unconnected-(U9-TX_ALT-Pad3)") (class "Default")
      (node (ref "U9") (pin "3") (pinfunction "TX_ALT_3") (pintype "bidirectional"))
    )
    (net (code "201") (name "unconnected-(U11-RFO-Pad23)") (class "Default")
      (node (ref "U11") (pin "23") (pinfunction "RFO_23") (pintype "bidirectional"))
    )
    (net (code "202") (name "unconnected-(U11-VR_PA-Pad24)") (class "Default")
      (node (ref "U11") (pin "24") (pinfunction "VR_PA_24") (pintype "bidirectional"))
    )
    (net (code "203") (name "unconnected-(U11-XTB-Pad4)") (class "Default")
      (node (ref "U11") (pin "4") (pinfunction "XTB_4") (pintype "bidirectional"))
    )
    (net (code "204") (name "unconnected-(U12-PA1-Pad7)") (class "Default")
      (node (ref "U12") (pin "7") (pinfunction "PA1_7") (pintype "bidirectional"))
    )
    (net (code "205") (name "unconnected-(U12-PA9-Pad19)") (class "Default")
      (node (ref "U12") (pin "19") (pinfunction "PA9_19") (pintype "bidirectional"))
    )
    (net (code "206") (name "unconnected-(U12-PA10-Pad20)") (class "Default")
      (node (ref "U12") (pin "20") (pinfunction "PA10_20") (pintype "bidirectional"))
    )
    (net (code "207") (name "unconnected-(U12-PA15-Pad25)") (class "Default")
      (node (ref "U12") (pin "25") (pinfunction "PA15_25") (pintype "bidirectional"))
    )
    (net (code "208") (name "unconnected-(U12-PB5-Pad28)") (class "Default")
      (node (ref "U12") (pin "28") (pinfunction "PB5_28") (pintype "bidirectional"))
    )
  )
)
